# SM3320-BATT-EV.net
KiCad netlist of a schematic drawn in Altium Designer
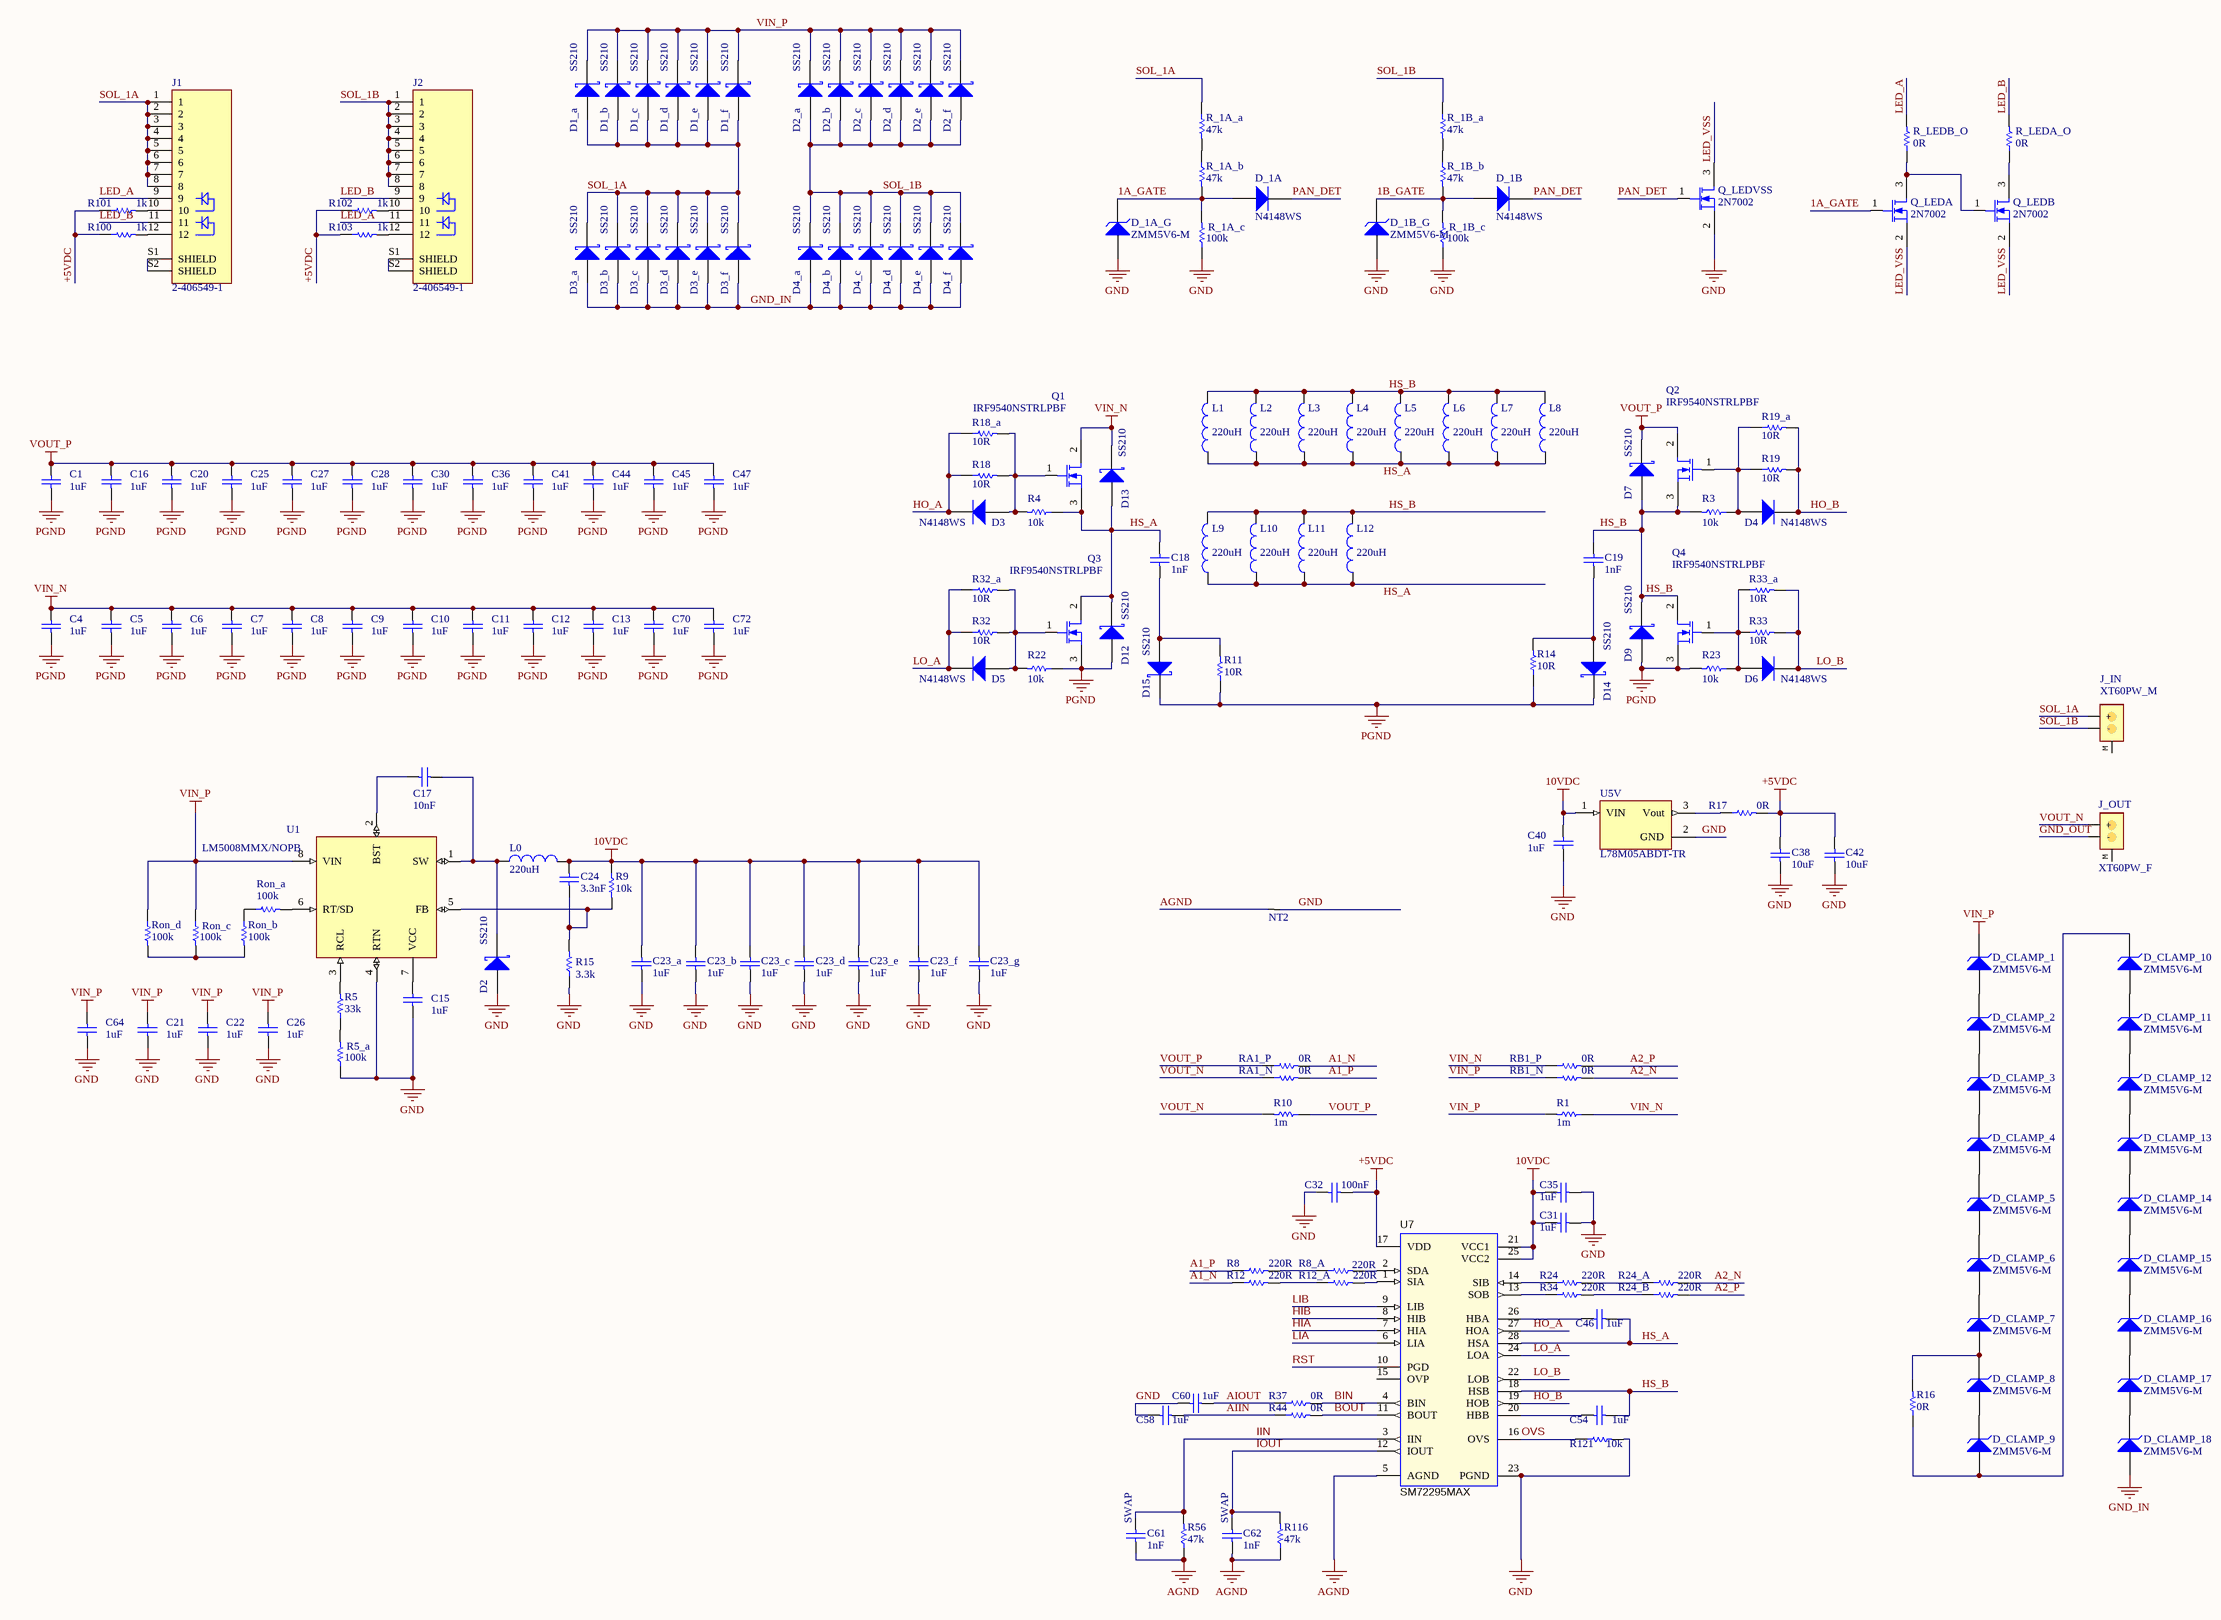
[diagram p0: SM3320-BATT-EV.SchDoc]

(export (version "E")
  (design (tool "Eeschema 10.0.6"))
  (components
    (comp (ref "C1")
      (value "1uF")
      (footprint "C_1206")
      (description "C - CAPACITOR - MLCC - 1uF - 100V - 1206 - X7R")
      (fields (field (name "LCSC PART #") "C91151") (field (name "Comment") "1206B105K101NT"))
      (libsource (lib "JLC_PCB") (part "1206B105K101NT"))
    )
    (comp (ref "C4")
      (value "1uF")
      (footprint "C_1206")
      (description "C - CAPACITOR - MLCC - 1uF - 100V - 1206 - X7R")
      (fields (field (name "LCSC PART #") "C91151") (field (name "Comment") "1206B105K101NT"))
      (libsource (lib "JLC_PCB") (part "1206B105K101NT"))
    )
    (comp (ref "C5")
      (value "1uF")
      (footprint "C_1206")
      (description "C - CAPACITOR - MLCC - 1uF - 100V - 1206 - X7R")
      (fields (field (name "LCSC PART #") "C91151") (field (name "Comment") "1206B105K101NT"))
      (libsource (lib "JLC_PCB") (part "1206B105K101NT"))
    )
    (comp (ref "C6")
      (value "1uF")
      (footprint "C_1206")
      (description "C - CAPACITOR - MLCC - 1uF - 100V - 1206 - X7R")
      (fields (field (name "LCSC PART #") "C91151") (field (name "Comment") "1206B105K101NT"))
      (libsource (lib "JLC_PCB") (part "1206B105K101NT"))
    )
    (comp (ref "C7")
      (value "1uF")
      (footprint "C_1206")
      (description "C - CAPACITOR - MLCC - 1uF - 100V - 1206 - X7R")
      (fields (field (name "LCSC PART #") "C91151") (field (name "Comment") "1206B105K101NT"))
      (libsource (lib "JLC_PCB") (part "1206B105K101NT"))
    )
    (comp (ref "C8")
      (value "1uF")
      (footprint "C_1206")
      (description "C - CAPACITOR - MLCC - 1uF - 100V - 1206 - X7R")
      (fields (field (name "LCSC PART #") "C91151") (field (name "Comment") "1206B105K101NT"))
      (libsource (lib "JLC_PCB") (part "1206B105K101NT"))
    )
    (comp (ref "C9")
      (value "1uF")
      (footprint "C_1206")
      (description "C - CAPACITOR - MLCC - 1uF - 100V - 1206 - X7R")
      (fields (field (name "LCSC PART #") "C91151") (field (name "Comment") "1206B105K101NT"))
      (libsource (lib "JLC_PCB") (part "1206B105K101NT"))
    )
    (comp (ref "C10")
      (value "1uF")
      (footprint "C_1206")
      (description "C - CAPACITOR - MLCC - 1uF - 100V - 1206 - X7R")
      (fields (field (name "LCSC PART #") "C91151") (field (name "Comment") "1206B105K101NT"))
      (libsource (lib "JLC_PCB") (part "1206B105K101NT"))
    )
    (comp (ref "C11")
      (value "1uF")
      (footprint "C_1206")
      (description "C - CAPACITOR - MLCC - 1uF - 100V - 1206 - X7R")
      (fields (field (name "LCSC PART #") "C91151") (field (name "Comment") "1206B105K101NT"))
      (libsource (lib "JLC_PCB") (part "1206B105K101NT"))
    )
    (comp (ref "C12")
      (value "1uF")
      (footprint "C_1206")
      (description "C - CAPACITOR - MLCC - 1uF - 100V - 1206 - X7R")
      (fields (field (name "LCSC PART #") "C91151") (field (name "Comment") "1206B105K101NT"))
      (libsource (lib "JLC_PCB") (part "1206B105K101NT"))
    )
    (comp (ref "C13")
      (value "1uF")
      (footprint "C_1206")
      (description "C - CAPACITOR - MLCC - 1uF - 100V - 1206 - X7R")
      (fields (field (name "LCSC PART #") "C91151") (field (name "Comment") "1206B105K101NT"))
      (libsource (lib "JLC_PCB") (part "1206B105K101NT"))
    )
    (comp (ref "C15")
      (value "1uF")
      (footprint "C_0402")
      (description "C - CAPACITOR - MLCC - 1uF - 25V - 0402")
      (fields (field (name "LCSC PART #") "C52923") (field (name "Comment") "CL05A105KA5NQNC"))
      (libsource (lib "JLC_PCB") (part "CL05A105KA5NQNC"))
    )
    (comp (ref "C16")
      (value "1uF")
      (footprint "C_1206")
      (description "C - CAPACITOR - MLCC - 1uF - 100V - 1206 - X7R")
      (fields (field (name "LCSC PART #") "C91151") (field (name "Comment") "1206B105K101NT"))
      (libsource (lib "JLC_PCB") (part "1206B105K101NT"))
    )
    (comp (ref "C17")
      (value "10nF")
      (footprint "C_0402")
      (description "C - CAPACITOR - MLCC - 10nF - 50V - 0402")
      (fields (field (name "LCSC PART #") "C15195") (field (name "Comment") "CL05B103KB5NNNC"))
      (libsource (lib "JLC_PCB") (part "CL05B103KB5NNNC"))
    )
    (comp (ref "C18")
      (value "1nF")
      (footprint "C_1206")
      (description "C - CAPACITOR - MLCC - 1nF - 2000V - 1206 - X7R")
      (fields (field (name "LCSC PART #") "C9196") (field (name "Comment") "1206B102K202NT"))
      (libsource (lib "JLC_PCB") (part "1206B102K202NT"))
    )
    (comp (ref "C19")
      (value "1nF")
      (footprint "C_1206")
      (description "C - CAPACITOR - MLCC - 1nF - 2000V - 1206 - X7R")
      (fields (field (name "LCSC PART #") "C9196") (field (name "Comment") "1206B102K202NT"))
      (libsource (lib "JLC_PCB") (part "1206B102K202NT"))
    )
    (comp (ref "C20")
      (value "1uF")
      (footprint "C_1206")
      (description "C - CAPACITOR - MLCC - 1uF - 100V - 1206 - X7R")
      (fields (field (name "LCSC PART #") "C91151") (field (name "Comment") "1206B105K101NT"))
      (libsource (lib "JLC_PCB") (part "1206B105K101NT"))
    )
    (comp (ref "C21")
      (value "1uF")
      (footprint "C_1206")
      (description "C - CAPACITOR - MLCC - 1uF - 100V - 1206 - X7R")
      (fields (field (name "LCSC PART #") "C91151") (field (name "Comment") "1206B105K101NT"))
      (libsource (lib "JLC_PCB") (part "1206B105K101NT"))
    )
    (comp (ref "C22")
      (value "1uF")
      (footprint "C_1206")
      (description "C - CAPACITOR - MLCC - 1uF - 100V - 1206 - X7R")
      (fields (field (name "LCSC PART #") "C91151") (field (name "Comment") "1206B105K101NT"))
      (libsource (lib "JLC_PCB") (part "1206B105K101NT"))
    )
    (comp (ref "C23_a")
      (value "1uF")
      (footprint "C_0402")
      (description "C - CAPACITOR - MLCC - 1uF - 25V - 0402")
      (fields (field (name "LCSC PART #") "C52923") (field (name "Comment") "CL05A105KA5NQNC"))
      (libsource (lib "JLC_PCB") (part "CL05A105KA5NQNC"))
    )
    (comp (ref "C23_b")
      (value "1uF")
      (footprint "C_0402")
      (description "C - CAPACITOR - MLCC - 1uF - 25V - 0402")
      (fields (field (name "LCSC PART #") "C52923") (field (name "Comment") "CL05A105KA5NQNC"))
      (libsource (lib "JLC_PCB") (part "CL05A105KA5NQNC"))
    )
    (comp (ref "C23_c")
      (value "1uF")
      (footprint "C_0402")
      (description "C - CAPACITOR - MLCC - 1uF - 25V - 0402")
      (fields (field (name "LCSC PART #") "C52923") (field (name "Comment") "CL05A105KA5NQNC"))
      (libsource (lib "JLC_PCB") (part "CL05A105KA5NQNC"))
    )
    (comp (ref "C23_d")
      (value "1uF")
      (footprint "C_0402")
      (description "C - CAPACITOR - MLCC - 1uF - 25V - 0402")
      (fields (field (name "LCSC PART #") "C52923") (field (name "Comment") "CL05A105KA5NQNC"))
      (libsource (lib "JLC_PCB") (part "CL05A105KA5NQNC"))
    )
    (comp (ref "C23_e")
      (value "1uF")
      (footprint "C_0402")
      (description "C - CAPACITOR - MLCC - 1uF - 25V - 0402")
      (fields (field (name "LCSC PART #") "C52923") (field (name "Comment") "CL05A105KA5NQNC"))
      (libsource (lib "JLC_PCB") (part "CL05A105KA5NQNC"))
    )
    (comp (ref "C23_f")
      (value "1uF")
      (footprint "C_0402")
      (description "C - CAPACITOR - MLCC - 1uF - 25V - 0402")
      (fields (field (name "LCSC PART #") "C52923") (field (name "Comment") "CL05A105KA5NQNC"))
      (libsource (lib "JLC_PCB") (part "CL05A105KA5NQNC"))
    )
    (comp (ref "C23_g")
      (value "1uF")
      (footprint "C_0402")
      (description "C - CAPACITOR - MLCC - 1uF - 25V - 0402")
      (fields (field (name "LCSC PART #") "C52923") (field (name "Comment") "CL05A105KA5NQNC"))
      (libsource (lib "JLC_PCB") (part "CL05A105KA5NQNC"))
    )
    (comp (ref "C24")
      (value "3.3nF")
      (footprint "C_0402")
      (description "C - CAPACITOR - MLCC - 3.3nF - 50V - 0402")
      (fields (field (name "LCSC PART #") "C26404") (field (name "Comment") "CL05B332KB5NNNC"))
      (libsource (lib "JLC_PCB") (part "CL05B332KB5NNNC"))
    )
    (comp (ref "C25")
      (value "1uF")
      (footprint "C_1206")
      (description "C - CAPACITOR - MLCC - 1uF - 100V - 1206 - X7R")
      (fields (field (name "LCSC PART #") "C91151") (field (name "Comment") "1206B105K101NT"))
      (libsource (lib "JLC_PCB") (part "1206B105K101NT"))
    )
    (comp (ref "C26")
      (value "1uF")
      (footprint "C_1206")
      (description "C - CAPACITOR - MLCC - 1uF - 100V - 1206 - X7R")
      (fields (field (name "LCSC PART #") "C91151") (field (name "Comment") "1206B105K101NT"))
      (libsource (lib "JLC_PCB") (part "1206B105K101NT"))
    )
    (comp (ref "C27")
      (value "1uF")
      (footprint "C_1206")
      (description "C - CAPACITOR - MLCC - 1uF - 100V - 1206 - X7R")
      (fields (field (name "LCSC PART #") "C91151") (field (name "Comment") "1206B105K101NT"))
      (libsource (lib "JLC_PCB") (part "1206B105K101NT"))
    )
    (comp (ref "C28")
      (value "1uF")
      (footprint "C_1206")
      (description "C - CAPACITOR - MLCC - 1uF - 100V - 1206 - X7R")
      (fields (field (name "LCSC PART #") "C91151") (field (name "Comment") "1206B105K101NT"))
      (libsource (lib "JLC_PCB") (part "1206B105K101NT"))
    )
    (comp (ref "C30")
      (value "1uF")
      (footprint "C_1206")
      (description "C - CAPACITOR - MLCC - 1uF - 100V - 1206 - X7R")
      (fields (field (name "LCSC PART #") "C91151") (field (name "Comment") "1206B105K101NT"))
      (libsource (lib "JLC_PCB") (part "1206B105K101NT"))
    )
    (comp (ref "C31")
      (value "1uF")
      (footprint "C_0402")
      (description "C - CAPACITOR - MLCC - 1uF - 25V - 0402")
      (fields (field (name "LCSC PART #") "C52923") (field (name "Comment") "CL05A105KA5NQNC"))
      (libsource (lib "JLC_PCB") (part "CL05A105KA5NQNC"))
    )
    (comp (ref "C32")
      (value "100nF")
      (footprint "C_0402")
      (description "C - CAPACITOR - MLCC - 100nF - 16V - 0402")
      (fields (field (name "LCSC PART #") "C1525") (field (name "Comment") "CL05B104KO5NNNC"))
      (libsource (lib "JLC_PCB") (part "CL05B104KO5NNNC"))
    )
    (comp (ref "C35")
      (value "1uF")
      (footprint "C_0402")
      (description "C - CAPACITOR - MLCC - 1uF - 25V - 0402")
      (fields (field (name "LCSC PART #") "C52923") (field (name "Comment") "CL05A105KA5NQNC"))
      (libsource (lib "JLC_PCB") (part "CL05A105KA5NQNC"))
    )
    (comp (ref "C36")
      (value "1uF")
      (footprint "C_1206")
      (description "C - CAPACITOR - MLCC - 1uF - 100V - 1206 - X7R")
      (fields (field (name "LCSC PART #") "C91151") (field (name "Comment") "1206B105K101NT"))
      (libsource (lib "JLC_PCB") (part "1206B105K101NT"))
    )
    (comp (ref "C38")
      (value "10uF")
      (footprint "C_0402")
      (description "C - CAPACITOR - MLCC - 10uF - 6.3V - 0402")
      (fields (field (name "LCSC PART #") "C15525") (field (name "Comment") "CL05A106MQ5NUNC"))
      (libsource (lib "JLC_PCB") (part "CL05A106MQ5NUNC"))
    )
    (comp (ref "C40")
      (value "1uF")
      (footprint "C_0402")
      (description "C - CAPACITOR - MLCC - 1uF - 25V - 0402")
      (fields (field (name "LCSC PART #") "C52923") (field (name "Comment") "CL05A105KA5NQNC"))
      (libsource (lib "JLC_PCB") (part "CL05A105KA5NQNC"))
    )
    (comp (ref "C41")
      (value "1uF")
      (footprint "C_1206")
      (description "C - CAPACITOR - MLCC - 1uF - 100V - 1206 - X7R")
      (fields (field (name "LCSC PART #") "C91151") (field (name "Comment") "1206B105K101NT"))
      (libsource (lib "JLC_PCB") (part "1206B105K101NT"))
    )
    (comp (ref "C42")
      (value "10uF")
      (footprint "C_0402")
      (description "C - CAPACITOR - MLCC - 10uF - 6.3V - 0402")
      (fields (field (name "LCSC PART #") "C15525") (field (name "Comment") "CL05A106MQ5NUNC"))
      (libsource (lib "JLC_PCB") (part "CL05A106MQ5NUNC"))
    )
    (comp (ref "C44")
      (value "1uF")
      (footprint "C_1206")
      (description "C - CAPACITOR - MLCC - 1uF - 100V - 1206 - X7R")
      (fields (field (name "LCSC PART #") "C91151") (field (name "Comment") "1206B105K101NT"))
      (libsource (lib "JLC_PCB") (part "1206B105K101NT"))
    )
    (comp (ref "C45")
      (value "1uF")
      (footprint "C_1206")
      (description "C - CAPACITOR - MLCC - 1uF - 100V - 1206 - X7R")
      (fields (field (name "LCSC PART #") "C91151") (field (name "Comment") "1206B105K101NT"))
      (libsource (lib "JLC_PCB") (part "1206B105K101NT"))
    )
    (comp (ref "C46")
      (value "1uF")
      (footprint "C_0402")
      (description "C - CAPACITOR - MLCC - 1uF - 25V - 0402")
      (fields (field (name "LCSC PART #") "C52923") (field (name "Comment") "CL05A105KA5NQNC"))
      (libsource (lib "JLC_PCB") (part "CL05A105KA5NQNC"))
    )
    (comp (ref "C47")
      (value "1uF")
      (footprint "C_1206")
      (description "C - CAPACITOR - MLCC - 1uF - 100V - 1206 - X7R")
      (fields (field (name "LCSC PART #") "C91151") (field (name "Comment") "1206B105K101NT"))
      (libsource (lib "JLC_PCB") (part "1206B105K101NT"))
    )
    (comp (ref "C54")
      (value "1uF")
      (footprint "C_0402")
      (description "C - CAPACITOR - MLCC - 1uF - 25V - 0402")
      (fields (field (name "LCSC PART #") "C52923") (field (name "Comment") "CL05A105KA5NQNC"))
      (libsource (lib "JLC_PCB") (part "CL05A105KA5NQNC"))
    )
    (comp (ref "C58")
      (value "1uF")
      (footprint "C_0402")
      (description "C - CAPACITOR - MLCC - 1uF - 25V - 0402")
      (fields (field (name "LCSC PART #") "C52923") (field (name "Comment") "CL05A105KA5NQNC"))
      (libsource (lib "JLC_PCB") (part "CL05A105KA5NQNC"))
    )
    (comp (ref "C60")
      (value "1uF")
      (footprint "C_0402")
      (description "C - CAPACITOR - MLCC - 1uF - 25V - 0402")
      (fields (field (name "LCSC PART #") "C52923") (field (name "Comment") "CL05A105KA5NQNC"))
      (libsource (lib "JLC_PCB") (part "CL05A105KA5NQNC"))
    )
    (comp (ref "C61")
      (value "1nF")
      (footprint "C_0402")
      (description "C - CAPACITOR - MLCC - 1nF - 50V - 0402")
      (fields (field (name "LCSC PART #") "C1523") (field (name "Comment") "0402B102K500NT"))
      (libsource (lib "JLC_PCB") (part "0402B102K500NT"))
    )
    (comp (ref "C62")
      (value "1nF")
      (footprint "C_0402")
      (description "C - CAPACITOR - MLCC - 1nF - 50V - 0402")
      (fields (field (name "LCSC PART #") "C1523") (field (name "Comment") "0402B102K500NT"))
      (libsource (lib "JLC_PCB") (part "0402B102K500NT"))
    )
    (comp (ref "C64")
      (value "1uF")
      (footprint "C_1206")
      (description "C - CAPACITOR - MLCC - 1uF - 100V - 1206 - X7R")
      (fields (field (name "LCSC PART #") "C91151") (field (name "Comment") "1206B105K101NT"))
      (libsource (lib "JLC_PCB") (part "1206B105K101NT"))
    )
    (comp (ref "C70")
      (value "1uF")
      (footprint "C_1206")
      (description "C - CAPACITOR - MLCC - 1uF - 100V - 1206 - X7R")
      (fields (field (name "LCSC PART #") "C91151") (field (name "Comment") "1206B105K101NT"))
      (libsource (lib "JLC_PCB") (part "1206B105K101NT"))
    )
    (comp (ref "C72")
      (value "1uF")
      (footprint "C_1206")
      (description "C - CAPACITOR - MLCC - 1uF - 100V - 1206 - X7R")
      (fields (field (name "LCSC PART #") "C91151") (field (name "Comment") "1206B105K101NT"))
      (libsource (lib "JLC_PCB") (part "1206B105K101NT"))
    )
    (comp (ref "D1_a")
      (value "SS210")
      (footprint "DO-214AC")
      (description "D - DIODE - SCHOTTKY - 100V - 2A")
      (fields (field (name "LCSC PART #") "C14996"))
      (libsource (lib "JLC_PCB") (part "SS210"))
    )
    (comp (ref "D1_b")
      (value "SS210")
      (footprint "DO-214AC")
      (description "D - DIODE - SCHOTTKY - 100V - 2A")
      (fields (field (name "LCSC PART #") "C14996"))
      (libsource (lib "JLC_PCB") (part "SS210"))
    )
    (comp (ref "D1_c")
      (value "SS210")
      (footprint "DO-214AC")
      (description "D - DIODE - SCHOTTKY - 100V - 2A")
      (fields (field (name "LCSC PART #") "C14996"))
      (libsource (lib "JLC_PCB") (part "SS210"))
    )
    (comp (ref "D1_d")
      (value "SS210")
      (footprint "DO-214AC")
      (description "D - DIODE - SCHOTTKY - 100V - 2A")
      (fields (field (name "LCSC PART #") "C14996"))
      (libsource (lib "JLC_PCB") (part "SS210"))
    )
    (comp (ref "D1_e")
      (value "SS210")
      (footprint "DO-214AC")
      (description "D - DIODE - SCHOTTKY - 100V - 2A")
      (fields (field (name "LCSC PART #") "C14996"))
      (libsource (lib "JLC_PCB") (part "SS210"))
    )
    (comp (ref "D1_f")
      (value "SS210")
      (footprint "DO-214AC")
      (description "D - DIODE - SCHOTTKY - 100V - 2A")
      (fields (field (name "LCSC PART #") "C14996"))
      (libsource (lib "JLC_PCB") (part "SS210"))
    )
    (comp (ref "D2")
      (value "SS210")
      (footprint "DO-214AC")
      (description "D - DIODE - SCHOTTKY - 100V - 2A")
      (fields (field (name "LCSC PART #") "C14996"))
      (libsource (lib "JLC_PCB") (part "SS210"))
    )
    (comp (ref "D2_a")
      (value "SS210")
      (footprint "DO-214AC")
      (description "D - DIODE - SCHOTTKY - 100V - 2A")
      (fields (field (name "LCSC PART #") "C14996"))
      (libsource (lib "JLC_PCB") (part "SS210"))
    )
    (comp (ref "D2_b")
      (value "SS210")
      (footprint "DO-214AC")
      (description "D - DIODE - SCHOTTKY - 100V - 2A")
      (fields (field (name "LCSC PART #") "C14996"))
      (libsource (lib "JLC_PCB") (part "SS210"))
    )
    (comp (ref "D2_c")
      (value "SS210")
      (footprint "DO-214AC")
      (description "D - DIODE - SCHOTTKY - 100V - 2A")
      (fields (field (name "LCSC PART #") "C14996"))
      (libsource (lib "JLC_PCB") (part "SS210"))
    )
    (comp (ref "D2_d")
      (value "SS210")
      (footprint "DO-214AC")
      (description "D - DIODE - SCHOTTKY - 100V - 2A")
      (fields (field (name "LCSC PART #") "C14996"))
      (libsource (lib "JLC_PCB") (part "SS210"))
    )
    (comp (ref "D2_e")
      (value "SS210")
      (footprint "DO-214AC")
      (description "D - DIODE - SCHOTTKY - 100V - 2A")
      (fields (field (name "LCSC PART #") "C14996"))
      (libsource (lib "JLC_PCB") (part "SS210"))
    )
    (comp (ref "D2_f")
      (value "SS210")
      (footprint "DO-214AC")
      (description "D - DIODE - SCHOTTKY - 100V - 2A")
      (fields (field (name "LCSC PART #") "C14996"))
      (libsource (lib "JLC_PCB") (part "SS210"))
    )
    (comp (ref "D3")
      (value "N4148WS")
      (footprint "SOD-323")
      (description "D - DIODE - FAST TRR - 100V - 150mA - 4ns")
      (fields (field (name "LCSC PART #") "C2128"))
      (libsource (lib "JLC_PCB") (part "N4148WS"))
    )
    (comp (ref "D3_a")
      (value "SS210")
      (footprint "DO-214AC")
      (description "D - DIODE - SCHOTTKY - 100V - 2A")
      (fields (field (name "LCSC PART #") "C14996"))
      (libsource (lib "JLC_PCB") (part "SS210"))
    )
    (comp (ref "D3_b")
      (value "SS210")
      (footprint "DO-214AC")
      (description "D - DIODE - SCHOTTKY - 100V - 2A")
      (fields (field (name "LCSC PART #") "C14996"))
      (libsource (lib "JLC_PCB") (part "SS210"))
    )
    (comp (ref "D3_c")
      (value "SS210")
      (footprint "DO-214AC")
      (description "D - DIODE - SCHOTTKY - 100V - 2A")
      (fields (field (name "LCSC PART #") "C14996"))
      (libsource (lib "JLC_PCB") (part "SS210"))
    )
    (comp (ref "D3_d")
      (value "SS210")
      (footprint "DO-214AC")
      (description "D - DIODE - SCHOTTKY - 100V - 2A")
      (fields (field (name "LCSC PART #") "C14996"))
      (libsource (lib "JLC_PCB") (part "SS210"))
    )
    (comp (ref "D3_e")
      (value "SS210")
      (footprint "DO-214AC")
      (description "D - DIODE - SCHOTTKY - 100V - 2A")
      (fields (field (name "LCSC PART #") "C14996"))
      (libsource (lib "JLC_PCB") (part "SS210"))
    )
    (comp (ref "D3_f")
      (value "SS210")
      (footprint "DO-214AC")
      (description "D - DIODE - SCHOTTKY - 100V - 2A")
      (fields (field (name "LCSC PART #") "C14996"))
      (libsource (lib "JLC_PCB") (part "SS210"))
    )
    (comp (ref "D4")
      (value "N4148WS")
      (footprint "SOD-323")
      (description "D - DIODE - FAST TRR - 100V - 150mA - 4ns")
      (fields (field (name "LCSC PART #") "C2128"))
      (libsource (lib "JLC_PCB") (part "N4148WS"))
    )
    (comp (ref "D4_a")
      (value "SS210")
      (footprint "DO-214AC")
      (description "D - DIODE - SCHOTTKY - 100V - 2A")
      (fields (field (name "LCSC PART #") "C14996"))
      (libsource (lib "JLC_PCB") (part "SS210"))
    )
    (comp (ref "D4_b")
      (value "SS210")
      (footprint "DO-214AC")
      (description "D - DIODE - SCHOTTKY - 100V - 2A")
      (fields (field (name "LCSC PART #") "C14996"))
      (libsource (lib "JLC_PCB") (part "SS210"))
    )
    (comp (ref "D4_c")
      (value "SS210")
      (footprint "DO-214AC")
      (description "D - DIODE - SCHOTTKY - 100V - 2A")
      (fields (field (name "LCSC PART #") "C14996"))
      (libsource (lib "JLC_PCB") (part "SS210"))
    )
    (comp (ref "D4_d")
      (value "SS210")
      (footprint "DO-214AC")
      (description "D - DIODE - SCHOTTKY - 100V - 2A")
      (fields (field (name "LCSC PART #") "C14996"))
      (libsource (lib "JLC_PCB") (part "SS210"))
    )
    (comp (ref "D4_e")
      (value "SS210")
      (footprint "DO-214AC")
      (description "D - DIODE - SCHOTTKY - 100V - 2A")
      (fields (field (name "LCSC PART #") "C14996"))
      (libsource (lib "JLC_PCB") (part "SS210"))
    )
    (comp (ref "D4_f")
      (value "SS210")
      (footprint "DO-214AC")
      (description "D - DIODE - SCHOTTKY - 100V - 2A")
      (fields (field (name "LCSC PART #") "C14996"))
      (libsource (lib "JLC_PCB") (part "SS210"))
    )
    (comp (ref "D5")
      (value "N4148WS")
      (footprint "SOD-323")
      (description "D - DIODE - FAST TRR - 100V - 150mA - 4ns")
      (fields (field (name "LCSC PART #") "C2128"))
      (libsource (lib "JLC_PCB") (part "N4148WS"))
    )
    (comp (ref "D6")
      (value "N4148WS")
      (footprint "SOD-323")
      (description "D - DIODE - FAST TRR - 100V - 150mA - 4ns")
      (fields (field (name "LCSC PART #") "C2128"))
      (libsource (lib "JLC_PCB") (part "N4148WS"))
    )
    (comp (ref "D7")
      (value "SS210")
      (footprint "DO-214AC")
      (description "D - DIODE - SCHOTTKY - 100V - 2A")
      (fields (field (name "LCSC PART #") "C14996"))
      (libsource (lib "JLC_PCB") (part "SS210"))
    )
    (comp (ref "D9")
      (value "SS210")
      (footprint "DO-214AC")
      (description "D - DIODE - SCHOTTKY - 100V - 2A")
      (fields (field (name "LCSC PART #") "C14996"))
      (libsource (lib "JLC_PCB") (part "SS210"))
    )
    (comp (ref "D12")
      (value "SS210")
      (footprint "DO-214AC")
      (description "D - DIODE - SCHOTTKY - 100V - 2A")
      (fields (field (name "LCSC PART #") "C14996"))
      (libsource (lib "JLC_PCB") (part "SS210"))
    )
    (comp (ref "D13")
      (value "SS210")
      (footprint "DO-214AC")
      (description "D - DIODE - SCHOTTKY - 100V - 2A")
      (fields (field (name "LCSC PART #") "C14996"))
      (libsource (lib "JLC_PCB") (part "SS210"))
    )
    (comp (ref "D14")
      (value "SS210")
      (footprint "DO-214AC")
      (description "D - DIODE - SCHOTTKY - 100V - 2A")
      (fields (field (name "LCSC PART #") "C14996"))
      (libsource (lib "JLC_PCB") (part "SS210"))
    )
    (comp (ref "D15")
      (value "SS210")
      (footprint "DO-214AC")
      (description "D - DIODE - SCHOTTKY - 100V - 2A")
      (fields (field (name "LCSC PART #") "C14996"))
      (libsource (lib "JLC_PCB") (part "SS210"))
    )
    (comp (ref "D_1A")
      (value "N4148WS")
      (footprint "SOD-323")
      (description "D - DIODE - FAST TRR - 100V - 150mA - 4ns")
      (fields (field (name "LCSC PART #") "C2128"))
      (libsource (lib "JLC_PCB") (part "N4148WS"))
    )
    (comp (ref "D_1A_G")
      (value "ZMM5V6-M")
      (footprint "DO-213AA")
      (description "D - DIODE - ZENER - 5.6V - 500mW")
      (fields (field (name "LCSC PART #") "C8062"))
      (libsource (lib "JLC_PCB") (part "ZMM5V6-M"))
    )
    (comp (ref "D_1B")
      (value "N4148WS")
      (footprint "SOD-323")
      (description "D - DIODE - FAST TRR - 100V - 150mA - 4ns")
      (fields (field (name "LCSC PART #") "C2128"))
      (libsource (lib "JLC_PCB") (part "N4148WS"))
    )
    (comp (ref "D_1B_G")
      (value "ZMM5V6-M")
      (footprint "DO-213AA")
      (description "D - DIODE - ZENER - 5.6V - 500mW")
      (fields (field (name "LCSC PART #") "C8062"))
      (libsource (lib "JLC_PCB") (part "ZMM5V6-M"))
    )
    (comp (ref "D_CLAMP_1")
      (value "ZMM5V6-M")
      (footprint "DO-213AA")
      (description "D - DIODE - ZENER - 5.6V - 500mW")
      (fields (field (name "LCSC PART #") "C8062"))
      (libsource (lib "JLC_PCB") (part "ZMM5V6-M"))
    )
    (comp (ref "D_CLAMP_2")
      (value "ZMM5V6-M")
      (footprint "DO-213AA")
      (description "D - DIODE - ZENER - 5.6V - 500mW")
      (fields (field (name "LCSC PART #") "C8062"))
      (libsource (lib "JLC_PCB") (part "ZMM5V6-M"))
    )
    (comp (ref "D_CLAMP_3")
      (value "ZMM5V6-M")
      (footprint "DO-213AA")
      (description "D - DIODE - ZENER - 5.6V - 500mW")
      (fields (field (name "LCSC PART #") "C8062"))
      (libsource (lib "JLC_PCB") (part "ZMM5V6-M"))
    )
    (comp (ref "D_CLAMP_4")
      (value "ZMM5V6-M")
      (footprint "DO-213AA")
      (description "D - DIODE - ZENER - 5.6V - 500mW")
      (fields (field (name "LCSC PART #") "C8062"))
      (libsource (lib "JLC_PCB") (part "ZMM5V6-M"))
    )
    (comp (ref "D_CLAMP_5")
      (value "ZMM5V6-M")
      (footprint "DO-213AA")
      (description "D - DIODE - ZENER - 5.6V - 500mW")
      (fields (field (name "LCSC PART #") "C8062"))
      (libsource (lib "JLC_PCB") (part "ZMM5V6-M"))
    )
    (comp (ref "D_CLAMP_6")
      (value "ZMM5V6-M")
      (footprint "DO-213AA")
      (description "D - DIODE - ZENER - 5.6V - 500mW")
      (fields (field (name "LCSC PART #") "C8062"))
      (libsource (lib "JLC_PCB") (part "ZMM5V6-M"))
    )
    (comp (ref "D_CLAMP_7")
      (value "ZMM5V6-M")
      (footprint "DO-213AA")
      (description "D - DIODE - ZENER - 5.6V - 500mW")
      (fields (field (name "LCSC PART #") "C8062"))
      (libsource (lib "JLC_PCB") (part "ZMM5V6-M"))
    )
    (comp (ref "D_CLAMP_8")
      (value "ZMM5V6-M")
      (footprint "DO-213AA")
      (description "D - DIODE - ZENER - 5.6V - 500mW")
      (fields (field (name "LCSC PART #") "C8062"))
      (libsource (lib "JLC_PCB") (part "ZMM5V6-M"))
    )
    (comp (ref "D_CLAMP_9")
      (value "ZMM5V6-M")
      (footprint "DO-213AA")
      (description "D - DIODE - ZENER - 5.6V - 500mW")
      (fields (field (name "LCSC PART #") "C8062"))
      (libsource (lib "JLC_PCB") (part "ZMM5V6-M"))
    )
    (comp (ref "D_CLAMP_10")
      (value "ZMM5V6-M")
      (footprint "DO-213AA")
      (description "D - DIODE - ZENER - 5.6V - 500mW")
      (fields (field (name "LCSC PART #") "C8062"))
      (libsource (lib "JLC_PCB") (part "ZMM5V6-M"))
    )
    (comp (ref "D_CLAMP_11")
      (value "ZMM5V6-M")
      (footprint "DO-213AA")
      (description "D - DIODE - ZENER - 5.6V - 500mW")
      (fields (field (name "LCSC PART #") "C8062"))
      (libsource (lib "JLC_PCB") (part "ZMM5V6-M"))
    )
    (comp (ref "D_CLAMP_12")
      (value "ZMM5V6-M")
      (footprint "DO-213AA")
      (description "D - DIODE - ZENER - 5.6V - 500mW")
      (fields (field (name "LCSC PART #") "C8062"))
      (libsource (lib "JLC_PCB") (part "ZMM5V6-M"))
    )
    (comp (ref "D_CLAMP_13")
      (value "ZMM5V6-M")
      (footprint "DO-213AA")
      (description "D - DIODE - ZENER - 5.6V - 500mW")
      (fields (field (name "LCSC PART #") "C8062"))
      (libsource (lib "JLC_PCB") (part "ZMM5V6-M"))
    )
    (comp (ref "D_CLAMP_14")
      (value "ZMM5V6-M")
      (footprint "DO-213AA")
      (description "D - DIODE - ZENER - 5.6V - 500mW")
      (fields (field (name "LCSC PART #") "C8062"))
      (libsource (lib "JLC_PCB") (part "ZMM5V6-M"))
    )
    (comp (ref "D_CLAMP_15")
      (value "ZMM5V6-M")
      (footprint "DO-213AA")
      (description "D - DIODE - ZENER - 5.6V - 500mW")
      (fields (field (name "LCSC PART #") "C8062"))
      (libsource (lib "JLC_PCB") (part "ZMM5V6-M"))
    )
    (comp (ref "D_CLAMP_16")
      (value "ZMM5V6-M")
      (footprint "DO-213AA")
      (description "D - DIODE - ZENER - 5.6V - 500mW")
      (fields (field (name "LCSC PART #") "C8062"))
      (libsource (lib "JLC_PCB") (part "ZMM5V6-M"))
    )
    (comp (ref "D_CLAMP_17")
      (value "ZMM5V6-M")
      (footprint "DO-213AA")
      (description "D - DIODE - ZENER - 5.6V - 500mW")
      (fields (field (name "LCSC PART #") "C8062"))
      (libsource (lib "JLC_PCB") (part "ZMM5V6-M"))
    )
    (comp (ref "D_CLAMP_18")
      (value "ZMM5V6-M")
      (footprint "DO-213AA")
      (description "D - DIODE - ZENER - 5.6V - 500mW")
      (fields (field (name "LCSC PART #") "C8062"))
      (libsource (lib "JLC_PCB") (part "ZMM5V6-M"))
    )
    (comp (ref "J1")
      (value "2-406549-1")
      (footprint "TE_2-406549-1")
      (description "J - JACK - ETHERNET - Right - THT")
      (fields (field (name "LCSC PART #") "C125068"))
      (libsource (lib "JLC_PCB") (part "2-406549-1"))
    )
    (comp (ref "J2")
      (value "2-406549-1")
      (footprint "TE_2-406549-1")
      (description "J - JACK - ETHERNET - Right - THT")
      (fields (field (name "LCSC PART #") "C125068"))
      (libsource (lib "JLC_PCB") (part "2-406549-1"))
    )
    (comp (ref "J_IN")
      (value "XT60PW_M")
      (footprint "XT60PW_M")
      (description "J - JACK - POWER - XT60 - RIGHT - MALE")
      (fields (field (name "LCSC PART #") "X"))
      (libsource (lib "JLC_PCB") (part "XT60PW_M"))
    )
    (comp (ref "J_OUT")
      (value "XT60PW_F")
      (footprint "XT60PW_F")
      (description "J - JACK - POWER - XT60 - RIGHT - FEMALE")
      (fields (field (name "LCSC PART #") "X"))
      (libsource (lib "JLC_PCB") (part "XT60PW_F"))
    )
    (comp (ref "L0")
      (value "220uH")
      (footprint "SRR1260")
      (description "L - INDUCTOR - 220uH - 1.6A - 12.5mm")
      (fields (field (name "LCSC PART #") "C169380") (field (name "Comment") "SWRB1207S-221MT"))
      (libsource (lib "JLC_PCB") (part "SWRB1207S-221MT"))
    )
    (comp (ref "L1")
      (value "220uH")
      (footprint "SRR1260")
      (description "L - INDUCTOR - 220uH - 1.6A - 12.5mm")
      (fields (field (name "LCSC PART #") "C169380") (field (name "Comment") "SWRB1207S-221MT"))
      (libsource (lib "JLC_PCB") (part "SWRB1207S-221MT"))
    )
    (comp (ref "L2")
      (value "220uH")
      (footprint "SRR1260")
      (description "L - INDUCTOR - 220uH - 1.6A - 12.5mm")
      (fields (field (name "LCSC PART #") "C169380") (field (name "Comment") "SWRB1207S-221MT"))
      (libsource (lib "JLC_PCB") (part "SWRB1207S-221MT"))
    )
    (comp (ref "L3")
      (value "220uH")
      (footprint "SRR1260")
      (description "L - INDUCTOR - 220uH - 1.6A - 12.5mm")
      (fields (field (name "LCSC PART #") "C169380") (field (name "Comment") "SWRB1207S-221MT"))
      (libsource (lib "JLC_PCB") (part "SWRB1207S-221MT"))
    )
    (comp (ref "L4")
      (value "220uH")
      (footprint "SRR1260")
      (description "L - INDUCTOR - 220uH - 1.6A - 12.5mm")
      (fields (field (name "LCSC PART #") "C169380") (field (name "Comment") "SWRB1207S-221MT"))
      (libsource (lib "JLC_PCB") (part "SWRB1207S-221MT"))
    )
    (comp (ref "L5")
      (value "220uH")
      (footprint "SRR1260")
      (description "L - INDUCTOR - 220uH - 1.6A - 12.5mm")
      (fields (field (name "LCSC PART #") "C169380") (field (name "Comment") "SWRB1207S-221MT"))
      (libsource (lib "JLC_PCB") (part "SWRB1207S-221MT"))
    )
    (comp (ref "L6")
      (value "220uH")
      (footprint "SRR1260")
      (description "L - INDUCTOR - 220uH - 1.6A - 12.5mm")
      (fields (field (name "LCSC PART #") "C169380") (field (name "Comment") "SWRB1207S-221MT"))
      (libsource (lib "JLC_PCB") (part "SWRB1207S-221MT"))
    )
    (comp (ref "L7")
      (value "220uH")
      (footprint "SRR1260")
      (description "L - INDUCTOR - 220uH - 1.6A - 12.5mm")
      (fields (field (name "LCSC PART #") "C169380") (field (name "Comment") "SWRB1207S-221MT"))
      (libsource (lib "JLC_PCB") (part "SWRB1207S-221MT"))
    )
    (comp (ref "L8")
      (value "220uH")
      (footprint "SRR1260")
      (description "L - INDUCTOR - 220uH - 1.6A - 12.5mm")
      (fields (field (name "LCSC PART #") "C169380") (field (name "Comment") "SWRB1207S-221MT"))
      (libsource (lib "JLC_PCB") (part "SWRB1207S-221MT"))
    )
    (comp (ref "L9")
      (value "220uH")
      (footprint "SRR1260")
      (description "L - INDUCTOR - 220uH - 1.6A - 12.5mm")
      (fields (field (name "LCSC PART #") "C169380") (field (name "Comment") "SWRB1207S-221MT"))
      (libsource (lib "JLC_PCB") (part "SWRB1207S-221MT"))
    )
    (comp (ref "L10")
      (value "220uH")
      (footprint "SRR1260")
      (description "L - INDUCTOR - 220uH - 1.6A - 12.5mm")
      (fields (field (name "LCSC PART #") "C169380") (field (name "Comment") "SWRB1207S-221MT"))
      (libsource (lib "JLC_PCB") (part "SWRB1207S-221MT"))
    )
    (comp (ref "L11")
      (value "220uH")
      (footprint "SRR1260")
      (description "L - INDUCTOR - 220uH - 1.6A - 12.5mm")
      (fields (field (name "LCSC PART #") "C169380") (field (name "Comment") "SWRB1207S-221MT"))
      (libsource (lib "JLC_PCB") (part "SWRB1207S-221MT"))
    )
    (comp (ref "L12")
      (value "220uH")
      (footprint "SRR1260")
      (description "L - INDUCTOR - 220uH - 1.6A - 12.5mm")
      (fields (field (name "LCSC PART #") "C169380") (field (name "Comment") "SWRB1207S-221MT"))
      (libsource (lib "JLC_PCB") (part "SWRB1207S-221MT"))
    )
    (comp (ref "NT2")
      (value "0")
      (footprint "NET_TIE")
      (description "R - Net Tie")
      (libsource (lib "JLC_PCB") (part "NET_TIE"))
    )
    (comp (ref "Q1")
      (value "IRF9540NSTRLPBF")
      (footprint "TO-263-3")
      (description "Q - TRANSISTOR - MOSFET (N) - 250V - 33A - 0.094R")
      (fields (field (name "LCSC PART #") "C33903"))
      (libsource (lib "JLC_PCB") (part "IRF9540NSTRLPBF"))
    )
    (comp (ref "Q2")
      (value "IRF9540NSTRLPBF")
      (footprint "TO-263-3")
      (description "Q - TRANSISTOR - MOSFET (N) - 250V - 33A - 0.094R")
      (fields (field (name "LCSC PART #") "C33903"))
      (libsource (lib "JLC_PCB") (part "IRF9540NSTRLPBF"))
    )
    (comp (ref "Q3")
      (value "IRF9540NSTRLPBF")
      (footprint "TO-263-3")
      (description "Q - TRANSISTOR - MOSFET (N) - 250V - 33A - 0.094R")
      (fields (field (name "LCSC PART #") "C33903"))
      (libsource (lib "JLC_PCB") (part "IRF9540NSTRLPBF"))
    )
    (comp (ref "Q4")
      (value "IRF9540NSTRLPBF")
      (footprint "TO-263-3")
      (description "Q - TRANSISTOR - MOSFET (N) - 250V - 33A - 0.094R")
      (fields (field (name "LCSC PART #") "C33903"))
      (libsource (lib "JLC_PCB") (part "IRF9540NSTRLPBF"))
    )
    (comp (ref "Q_LEDA")
      (value "2N7002")
      (footprint "TO-236AB")
      (description "Q - TRANSISTOR - MOSFET (N) - 60V - 200mW")
      (fields (field (name "LCSC PART #") "C8545"))
      (libsource (lib "JLC_PCB") (part "2N7002"))
    )
    (comp (ref "Q_LEDB")
      (value "2N7002")
      (footprint "TO-236AB")
      (description "Q - TRANSISTOR - MOSFET (N) - 60V - 200mW")
      (fields (field (name "LCSC PART #") "C8545"))
      (libsource (lib "JLC_PCB") (part "2N7002"))
    )
    (comp (ref "Q_LEDVSS")
      (value "2N7002")
      (footprint "TO-236AB")
      (description "Q - TRANSISTOR - MOSFET (N) - 60V - 200mW")
      (fields (field (name "LCSC PART #") "C8545"))
      (libsource (lib "JLC_PCB") (part "2N7002"))
    )
    (comp (ref "R1")
      (value "1m")
      (footprint "R_2512")
      (description "R - RESISTOR - SMD - 0.001R - 1% - 2512 - 2W - 50ppm/k")
      (fields (field (name "LCSC PART #") "C349153") (field (name "POWER") "2W"))
      (libsource (lib "JLC_PCB") (part "EWSL2512F1L00S9"))
    )
    (comp (ref "R3")
      (value "10k")
      (footprint "R_0402")
      (description "R - RESISTOR - SMD - 10k - 1% - 0402")
      (fields (field (name "LCSC PART #") "C25744") (field (name "Comment") "0402WGF1002TCE"))
      (libsource (lib "JLC_PCB") (part "0402WGF1002TCE"))
    )
    (comp (ref "R4")
      (value "10k")
      (footprint "R_0402")
      (description "R - RESISTOR - SMD - 10k - 1% - 0402")
      (fields (field (name "LCSC PART #") "C25744") (field (name "Comment") "0402WGF1002TCE"))
      (libsource (lib "JLC_PCB") (part "0402WGF1002TCE"))
    )
    (comp (ref "R5")
      (value "33k")
      (footprint "R_0402")
      (description "R - RESISTOR - SMD - 33k - 1% - 0402")
      (fields (field (name "LCSC PART #") "C25779") (field (name "Comment") "0402WGF3302TCE"))
      (libsource (lib "JLC_PCB") (part "0402WGF3302TCE"))
    )
    (comp (ref "R5_a")
      (value "100k")
      (footprint "R_0402")
      (description "R - RESISTOR - SMD - 100k - 1% -  0402")
      (fields (field (name "LCSC PART #") "C25741") (field (name "Comment") "0402WGF1003TCE"))
      (libsource (lib "JLC_PCB") (part "0402WGF1003TCE"))
    )
    (comp (ref "R8")
      (value "220R")
      (footprint "R_0402")
      (description "R - RESISTOR - SMD - 220R - 1% - 0402")
      (fields (field (name "LCSC PART #") "C25091") (field (name "Comment") "0402WGF2200TCE"))
      (libsource (lib "JLC_PCB") (part "0402WGF2200TCE"))
    )
    (comp (ref "R8_A")
      (value "220R")
      (footprint "R_0402")
      (description "R - RESISTOR - SMD - 220R - 1% - 0402")
      (fields (field (name "LCSC PART #") "C25091"))
      (libsource (lib "*") (part "0402WGF2200TCE"))
    )
    (comp (ref "R9")
      (value "10k")
      (footprint "R_0402")
      (description "R - RESISTOR - SMD - 10k - 1% - 0402")
      (fields (field (name "LCSC PART #") "C25744") (field (name "Comment") "0402WGF1002TCE"))
      (libsource (lib "JLC_PCB") (part "0402WGF1002TCE"))
    )
    (comp (ref "R10")
      (value "1m")
      (footprint "R_2512")
      (description "R - RESISTOR - SMD - 0.001R - 1% - 2512 - 2W - 50ppm/k")
      (fields (field (name "LCSC PART #") "C349153") (field (name "POWER") "2W"))
      (libsource (lib "JLC_PCB") (part "EWSL2512F1L00S9"))
    )
    (comp (ref "R11")
      (value "10R")
      (footprint "R_1206")
      (description "R - RESISTOR - SMD - 10R - 1% - 1206")
      (fields (field (name "LCSC PART #") "C17903") (field (name "Comment") "1206W4F100JT5E"))
      (libsource (lib "JLC_PCB") (part "1206W4F100JT5E"))
    )
    (comp (ref "R12")
      (value "220R")
      (footprint "R_0402")
      (description "R - RESISTOR - SMD - 220R - 1% - 0402")
      (fields (field (name "LCSC PART #") "C25091") (field (name "Comment") "0402WGF2200TCE"))
      (libsource (lib "JLC_PCB") (part "0402WGF2200TCE"))
    )
    (comp (ref "R12_A")
      (value "220R")
      (footprint "R_0402")
      (description "R - RESISTOR - SMD - 220R - 1% - 0402")
      (fields (field (name "LCSC PART #") "C25091") (field (name "Comment") "0402WGF2200TCE"))
      (libsource (lib "JLC_PCB") (part "0402WGF2200TCE"))
    )
    (comp (ref "R14")
      (value "10R")
      (footprint "R_1206")
      (description "R - RESISTOR - SMD - 10R - 1% - 1206")
      (fields (field (name "LCSC PART #") "C17903") (field (name "Comment") "1206W4F100JT5E"))
      (libsource (lib "JLC_PCB") (part "1206W4F100JT5E"))
    )
    (comp (ref "R15")
      (value "3.3k")
      (footprint "R_0402")
      (description "R - RESISTOR - SMD - 3.3k - 1% - 0402")
      (fields (field (name "LCSC PART #") "C25890") (field (name "Comment") "0402WGF3301TCE"))
      (libsource (lib "JLC_PCB") (part "0402WGF3301TCE"))
    )
    (comp (ref "R16")
      (value "0R")
      (footprint "R_0402")
      (description "R - RESISTOR - SMD - 0R - 1% - 0402")
      (fields (field (name "LCSC PART #") "C17168") (field (name "Comment") "0402WGF0000TCE"))
      (libsource (lib "JLC_PCB") (part "0402WGF0000TCE"))
    )
    (comp (ref "R17")
      (value "0R")
      (footprint "R_0402")
      (description "R - RESISTOR - SMD - 0R - 1% - 0402")
      (fields (field (name "LCSC PART #") "C17168") (field (name "Comment") "0402WGF0000TCE"))
      (libsource (lib "JLC_PCB") (part "0402WGF0000TCE"))
    )
    (comp (ref "R18")
      (value "10R")
      (footprint "R_0402")
      (description "R - RESISTOR - SMD - 10R - 1% - 0402")
      (fields (field (name "LCSC PART #") "C25077") (field (name "Comment") "0402WGF100JTCE"))
      (libsource (lib "JLC_PCB") (part "0402WGF100JTCE"))
    )
    (comp (ref "R18_a")
      (value "10R")
      (footprint "R_0402")
      (description "R - RESISTOR - SMD - 10R - 1% - 0402")
      (fields (field (name "LCSC PART #") "C25077") (field (name "Comment") "0402WGF100JTCE"))
      (libsource (lib "JLC_PCB") (part "0402WGF100JTCE"))
    )
    (comp (ref "R19")
      (value "10R")
      (footprint "R_0402")
      (description "R - RESISTOR - SMD - 10R - 1% - 0402")
      (fields (field (name "LCSC PART #") "C25077") (field (name "Comment") "0402WGF100JTCE"))
      (libsource (lib "JLC_PCB") (part "0402WGF100JTCE"))
    )
    (comp (ref "R19_a")
      (value "10R")
      (footprint "R_0402")
      (description "R - RESISTOR - SMD - 10R - 1% - 0402")
      (fields (field (name "LCSC PART #") "C25077") (field (name "Comment") "0402WGF100JTCE"))
      (libsource (lib "JLC_PCB") (part "0402WGF100JTCE"))
    )
    (comp (ref "R22")
      (value "10k")
      (footprint "R_0402")
      (description "R - RESISTOR - SMD - 10k - 1% - 0402")
      (fields (field (name "LCSC PART #") "C25744") (field (name "Comment") "0402WGF1002TCE"))
      (libsource (lib "JLC_PCB") (part "0402WGF1002TCE"))
    )
    (comp (ref "R23")
      (value "10k")
      (footprint "R_0402")
      (description "R - RESISTOR - SMD - 10k - 1% - 0402")
      (fields (field (name "LCSC PART #") "C25744") (field (name "Comment") "0402WGF1002TCE"))
      (libsource (lib "JLC_PCB") (part "0402WGF1002TCE"))
    )
    (comp (ref "R24")
      (value "220R")
      (footprint "R_0402")
      (description "R - RESISTOR - SMD - 220R - 1% - 0402")
      (fields (field (name "LCSC PART #") "C25091") (field (name "Comment") "0402WGF2200TCE"))
      (libsource (lib "JLC_PCB") (part "0402WGF2200TCE"))
    )
    (comp (ref "R24_A")
      (value "220R")
      (footprint "R_0402")
      (description "R - RESISTOR - SMD - 220R - 1% - 0402")
      (fields (field (name "LCSC PART #") "C25091") (field (name "Comment") "0402WGF2200TCE"))
      (libsource (lib "JLC_PCB") (part "0402WGF2200TCE"))
    )
    (comp (ref "R24_B")
      (value "220R")
      (footprint "R_0402")
      (description "R - RESISTOR - SMD - 220R - 1% - 0402")
      (fields (field (name "LCSC PART #") "C25091") (field (name "Comment") "0402WGF2200TCE"))
      (libsource (lib "JLC_PCB") (part "0402WGF2200TCE"))
    )
    (comp (ref "R32")
      (value "10R")
      (footprint "R_0402")
      (description "R - RESISTOR - SMD - 10R - 1% - 0402")
      (fields (field (name "LCSC PART #") "C25077") (field (name "Comment") "0402WGF100JTCE"))
      (libsource (lib "JLC_PCB") (part "0402WGF100JTCE"))
    )
    (comp (ref "R32_a")
      (value "10R")
      (footprint "R_0402")
      (description "R - RESISTOR - SMD - 10R - 1% - 0402")
      (fields (field (name "LCSC PART #") "C25077") (field (name "Comment") "0402WGF100JTCE"))
      (libsource (lib "JLC_PCB") (part "0402WGF100JTCE"))
    )
    (comp (ref "R33")
      (value "10R")
      (footprint "R_0402")
      (description "R - RESISTOR - SMD - 10R - 1% - 0402")
      (fields (field (name "LCSC PART #") "C25077") (field (name "Comment") "0402WGF100JTCE"))
      (libsource (lib "JLC_PCB") (part "0402WGF100JTCE"))
    )
    (comp (ref "R33_a")
      (value "10R")
      (footprint "R_0402")
      (description "R - RESISTOR - SMD - 10R - 1% - 0402")
      (fields (field (name "LCSC PART #") "C25077") (field (name "Comment") "0402WGF100JTCE"))
      (libsource (lib "JLC_PCB") (part "0402WGF100JTCE"))
    )
    (comp (ref "R34")
      (value "220R")
      (footprint "R_0402")
      (description "R - RESISTOR - SMD - 220R - 1% - 0402")
      (fields (field (name "LCSC PART #") "C25091") (field (name "Comment") "0402WGF2200TCE"))
      (libsource (lib "JLC_PCB") (part "0402WGF2200TCE"))
    )
    (comp (ref "R37")
      (value "0R")
      (footprint "R_0402")
      (description "R - RESISTOR - SMD - 0R - 1% - 0402")
      (fields (field (name "LCSC PART #") "C17168") (field (name "Comment") "0402WGF0000TCE"))
      (libsource (lib "JLC_PCB") (part "0402WGF0000TCE"))
    )
    (comp (ref "R44")
      (value "0R")
      (footprint "R_0402")
      (description "R - RESISTOR - SMD - 0R - 1% - 0402")
      (fields (field (name "LCSC PART #") "C17168") (field (name "Comment") "0402WGF0000TCE"))
      (libsource (lib "JLC_PCB") (part "0402WGF0000TCE"))
    )
    (comp (ref "R56")
      (value "47k")
      (footprint "R_0402")
      (description "R - RESISTOR - SMD - 47k - 1% - 0402")
      (fields (field (name "LCSC PART #") "C25792") (field (name "Comment") "0402WGF4702TCE"))
      (libsource (lib "JLC_PCB") (part "0402WGF4702TCE"))
    )
    (comp (ref "R100")
      (value "1k")
      (footprint "R_0402")
      (description "R - RESISTOR - SMD - 1k - 1% - 0402")
      (fields (field (name "LCSC PART #") "C11702") (field (name "Comment") "0402WGF1001TCE"))
      (libsource (lib "JLC_PCB") (part "0402WGF1001TCE"))
    )
    (comp (ref "R101")
      (value "1k")
      (footprint "R_0402")
      (description "R - RESISTOR - SMD - 1k - 1% - 0402")
      (fields (field (name "LCSC PART #") "C11702") (field (name "Comment") "0402WGF1001TCE"))
      (libsource (lib "JLC_PCB") (part "0402WGF1001TCE"))
    )
    (comp (ref "R102")
      (value "1k")
      (footprint "R_0402")
      (description "R - RESISTOR - SMD - 1k - 1% - 0402")
      (fields (field (name "LCSC PART #") "C11702") (field (name "Comment") "0402WGF1001TCE"))
      (libsource (lib "JLC_PCB") (part "0402WGF1001TCE"))
    )
    (comp (ref "R103")
      (value "1k")
      (footprint "R_0402")
      (description "R - RESISTOR - SMD - 1k - 1% - 0402")
      (fields (field (name "LCSC PART #") "C11702") (field (name "Comment") "0402WGF1001TCE"))
      (libsource (lib "JLC_PCB") (part "0402WGF1001TCE"))
    )
    (comp (ref "R116")
      (value "47k")
      (footprint "R_0402")
      (description "R - RESISTOR - SMD - 47k - 1% - 0402")
      (fields (field (name "LCSC PART #") "C25792") (field (name "Comment") "0402WGF4702TCE"))
      (libsource (lib "JLC_PCB") (part "0402WGF4702TCE"))
    )
    (comp (ref "R121")
      (value "10k")
      (footprint "R_0402")
      (description "R - RESISTOR - SMD - 10k - 1% - 0402")
      (fields (field (name "LCSC PART #") "C25744") (field (name "Comment") "0402WGF1002TCE"))
      (libsource (lib "JLC_PCB") (part "0402WGF1002TCE"))
    )
    (comp (ref "RA1_N")
      (value "0R")
      (footprint "R_0402")
      (description "R - RESISTOR - SMD - 0R - 1% - 0402")
      (fields (field (name "LCSC PART #") "C17168") (field (name "Comment") "0402WGF0000TCE"))
      (libsource (lib "JLC_PCB") (part "0402WGF0000TCE"))
    )
    (comp (ref "RA1_P")
      (value "0R")
      (footprint "R_0402")
      (description "R - RESISTOR - SMD - 0R - 1% - 0402")
      (fields (field (name "LCSC PART #") "C17168") (field (name "Comment") "0402WGF0000TCE"))
      (libsource (lib "JLC_PCB") (part "0402WGF0000TCE"))
    )
    (comp (ref "RB1_N")
      (value "0R")
      (footprint "R_0402")
      (description "R - RESISTOR - SMD - 0R - 1% - 0402")
      (fields (field (name "LCSC PART #") "C17168") (field (name "Comment") "0402WGF0000TCE"))
      (libsource (lib "JLC_PCB") (part "0402WGF0000TCE"))
    )
    (comp (ref "RB1_P")
      (value "0R")
      (footprint "R_0402")
      (description "R - RESISTOR - SMD - 0R - 1% - 0402")
      (fields (field (name "LCSC PART #") "C17168") (field (name "Comment") "0402WGF0000TCE"))
      (libsource (lib "JLC_PCB") (part "0402WGF0000TCE"))
    )
    (comp (ref "Ron_a")
      (value "100k")
      (footprint "R_0402")
      (description "R - RESISTOR - SMD - 100k - 1% -  0402")
      (fields (field (name "LCSC PART #") "C25741") (field (name "Comment") "0402WGF1003TCE"))
      (libsource (lib "JLC_PCB") (part "0402WGF1003TCE"))
    )
    (comp (ref "Ron_b")
      (value "100k")
      (footprint "R_0402")
      (description "R - RESISTOR - SMD - 100k - 1% -  0402")
      (fields (field (name "LCSC PART #") "C25741") (field (name "Comment") "0402WGF1003TCE"))
      (libsource (lib "JLC_PCB") (part "0402WGF1003TCE"))
    )
    (comp (ref "Ron_c")
      (value "100k")
      (footprint "R_0402")
      (description "R - RESISTOR - SMD - 100k - 1% -  0402")
      (fields (field (name "LCSC PART #") "C25741") (field (name "Comment") "0402WGF1003TCE"))
      (libsource (lib "JLC_PCB") (part "0402WGF1003TCE"))
    )
    (comp (ref "Ron_d")
      (value "100k")
      (footprint "R_0402")
      (description "R - RESISTOR - SMD - 100k - 1% -  0402")
      (fields (field (name "LCSC PART #") "C25741") (field (name "Comment") "0402WGF1003TCE"))
      (libsource (lib "JLC_PCB") (part "0402WGF1003TCE"))
    )
    (comp (ref "R_1A_a")
      (value "47k")
      (footprint "R_0402")
      (description "R - RESISTOR - SMD - 47k - 1% - 0402")
      (fields (field (name "LCSC PART #") "C25792") (field (name "Comment") "0402WGF4702TCE"))
      (libsource (lib "JLC_PCB") (part "0402WGF4702TCE"))
    )
    (comp (ref "R_1A_b")
      (value "47k")
      (footprint "R_0402")
      (description "R - RESISTOR - SMD - 47k - 1% - 0402")
      (fields (field (name "LCSC PART #") "C25792") (field (name "Comment") "0402WGF4702TCE"))
      (libsource (lib "JLC_PCB") (part "0402WGF4702TCE"))
    )
    (comp (ref "R_1A_c")
      (value "100k")
      (footprint "R_0402")
      (description "R - RESISTOR - SMD - 100k - 1% -  0402")
      (fields (field (name "LCSC PART #") "C25741") (field (name "Comment") "0402WGF1003TCE"))
      (libsource (lib "JLC_PCB") (part "0402WGF1003TCE"))
    )
    (comp (ref "R_1B_a")
      (value "47k")
      (footprint "R_0402")
      (description "R - RESISTOR - SMD - 47k - 1% - 0402")
      (fields (field (name "LCSC PART #") "C25792") (field (name "Comment") "0402WGF4702TCE"))
      (libsource (lib "JLC_PCB") (part "0402WGF4702TCE"))
    )
    (comp (ref "R_1B_b")
      (value "47k")
      (footprint "R_0402")
      (description "R - RESISTOR - SMD - 47k - 1% - 0402")
      (fields (field (name "LCSC PART #") "C25792") (field (name "Comment") "0402WGF4702TCE"))
      (libsource (lib "JLC_PCB") (part "0402WGF4702TCE"))
    )
    (comp (ref "R_1B_c")
      (value "100k")
      (footprint "R_0402")
      (description "R - RESISTOR - SMD - 100k - 1% -  0402")
      (fields (field (name "LCSC PART #") "C25741") (field (name "Comment") "0402WGF1003TCE"))
      (libsource (lib "JLC_PCB") (part "0402WGF1003TCE"))
    )
    (comp (ref "R_LEDA_O")
      (value "0R")
      (footprint "R_0402")
      (description "R - RESISTOR - SMD - 0R - 1% - 0402")
      (fields (field (name "LCSC PART #") "C17168") (field (name "Comment") "0402WGF0000TCE"))
      (libsource (lib "JLC_PCB") (part "0402WGF0000TCE"))
    )
    (comp (ref "R_LEDB_O")
      (value "0R")
      (footprint "R_0402")
      (description "R - RESISTOR - SMD - 0R - 1% - 0402")
      (fields (field (name "LCSC PART #") "C17168") (field (name "Comment") "0402WGF0000TCE"))
      (libsource (lib "JLC_PCB") (part "0402WGF0000TCE"))
    )
    (comp (ref "U1")
      (value "LM5008MMX/NOPB")
      (footprint "SOP65P490X110-8N")
      (description "U - IC - BUCK CONVERTER, ADJUSTABLE, 95V, 350mA")
      (libsource (lib "JLC_PCB") (part "LM5008MMX/NOPB"))
    )
    (comp (ref "U5V")
      (value "L78M05ABDT-TR")
      (footprint "TO-252AA")
      (description "U - IC - 5V Power Regulator")
      (fields (field (name "LCSC PART #") "C58069"))
      (libsource (lib "JLC_PCB") (part "L78M05ABDT-TR"))
    )
    (comp (ref "U7")
      (value "SM72295MAX")
      (footprint "M28B_M")
      (description "Photovoltaic Full Bridge Driver")
      (fields (field (name "MANUFACTURER") "National Semiconductor") (field (name "PARTNUMBER") "SM72295"))
      (libsource (lib "SM_ICs") (part "SM72295"))
    )
  )
  (nets
    (net (code "1") (name "+5VDC") (class "Default")
      (node (ref "C32") (pin "2") (pinfunction "2_2") (pintype "passive"))
      (node (ref "C38") (pin "2") (pinfunction "2_2") (pintype "passive"))
      (node (ref "C42") (pin "2") (pinfunction "2_2") (pintype "passive"))
      (node (ref "R100") (pin "1") (pinfunction "1_1") (pintype "passive"))
      (node (ref "R101") (pin "1") (pinfunction "1_1") (pintype "passive"))
      (node (ref "R102") (pin "1") (pinfunction "1_1") (pintype "passive"))
      (node (ref "R103") (pin "1") (pinfunction "1_1") (pintype "passive"))
      (node (ref "R17") (pin "2") (pinfunction "2_2") (pintype "passive"))
      (node (ref "U7") (pin "17") (pinfunction "VDD_17") (pintype "power_in"))
    )
    (net (code "2") (name "/1A_GATE") (class "Default")
      (node (ref "D_1A") (pin "2") (pinfunction "A_2") (pintype "passive"))
      (node (ref "D_1A_G") (pin "1") (pinfunction "K_1") (pintype "passive"))
      (node (ref "Q_LEDA") (pin "1") (pinfunction "G_1") (pintype "passive"))
      (node (ref "R_1A_b") (pin "2") (pinfunction "2_2") (pintype "passive"))
      (node (ref "R_1A_c") (pin "2") (pinfunction "2_2") (pintype "passive"))
    )
    (net (code "3") (name "/1B_GATE") (class "Default")
      (node (ref "D_1B") (pin "2") (pinfunction "A_2") (pintype "passive"))
      (node (ref "D_1B_G") (pin "1") (pinfunction "K_1") (pintype "passive"))
      (node (ref "R_1B_b") (pin "2") (pinfunction "2_2") (pintype "passive"))
      (node (ref "R_1B_c") (pin "2") (pinfunction "2_2") (pintype "passive"))
    )
    (net (code "4") (name "/A1_N") (class "Default")
      (node (ref "R12") (pin "1") (pinfunction "1_1") (pintype "passive"))
      (node (ref "RA1_P") (pin "2") (pinfunction "2_2") (pintype "passive"))
    )
    (net (code "5") (name "/A1_P") (class "Default")
      (node (ref "R8") (pin "1") (pinfunction "1_1") (pintype "passive"))
      (node (ref "RA1_N") (pin "2") (pinfunction "2_2") (pintype "passive"))
    )
    (net (code "6") (name "/A2_N") (class "Default")
      (node (ref "R24_A") (pin "2") (pinfunction "2_2") (pintype "passive"))
      (node (ref "RB1_N") (pin "2") (pinfunction "2_2") (pintype "passive"))
    )
    (net (code "7") (name "/A2_P") (class "Default")
      (node (ref "R24_B") (pin "2") (pinfunction "2_2") (pintype "passive"))
      (node (ref "RB1_P") (pin "2") (pinfunction "2_2") (pintype "passive"))
    )
    (net (code "8") (name "/AIIN") (class "Default")
      (node (ref "C58") (pin "2") (pinfunction "2_2") (pintype "passive"))
      (node (ref "R44") (pin "1") (pinfunction "1_1") (pintype "passive"))
    )
    (net (code "9") (name "/AIOUT") (class "Default")
      (node (ref "C60") (pin "2") (pinfunction "2_2") (pintype "passive"))
      (node (ref "R37") (pin "1") (pinfunction "1_1") (pintype "passive"))
    )
    (net (code "10") (name "/BIN") (class "Default")
      (node (ref "R37") (pin "2") (pinfunction "2_2") (pintype "passive"))
      (node (ref "U7") (pin "4") (pinfunction "BIN_4") (pintype "output"))
    )
    (net (code "11") (name "/BOUT") (class "Default")
      (node (ref "R44") (pin "2") (pinfunction "2_2") (pintype "passive"))
      (node (ref "U7") (pin "11") (pinfunction "BOUT_11") (pintype "output"))
    )
    (net (code "12") (name "/GND_OUT") (class "Default")
      (node (ref "J_OUT") (pin "MINUS") (pinfunction "-_MINUS") (pintype "passive"))
    )
    (net (code "13") (name "/HIA") (class "Default")
      (node (ref "U7") (pin "7") (pinfunction "HIA_7") (pintype "input"))
    )
    (net (code "14") (name "/HIB") (class "Default")
      (node (ref "U7") (pin "8") (pinfunction "HIB_8") (pintype "input"))
    )
    (net (code "15") (name "/HO_A") (class "Default")
      (node (ref "D3") (pin "1") (pinfunction "K_1") (pintype "passive"))
      (node (ref "R18") (pin "1") (pinfunction "1_1") (pintype "passive"))
      (node (ref "R18_a") (pin "1") (pinfunction "1_1") (pintype "passive"))
      (node (ref "U7") (pin "27") (pinfunction "HOA_27") (pintype "output"))
    )
    (net (code "16") (name "/HO_B") (class "Default")
      (node (ref "D4") (pin "1") (pinfunction "K_1") (pintype "passive"))
      (node (ref "R19") (pin "2") (pinfunction "2_2") (pintype "passive"))
      (node (ref "R19_a") (pin "2") (pinfunction "2_2") (pintype "passive"))
      (node (ref "U7") (pin "19") (pinfunction "HOB_19") (pintype "output"))
    )
    (net (code "17") (name "/HS_A") (class "Default")
      (node (ref "C18") (pin "2") (pinfunction "2_2") (pintype "passive"))
      (node (ref "C46") (pin "2") (pinfunction "2_2") (pintype "passive"))
      (node (ref "D12") (pin "1") (pinfunction "K_1") (pintype "passive"))
      (node (ref "D13") (pin "2") (pinfunction "A_2") (pintype "passive"))
      (node (ref "L1") (pin "1") (pinfunction "1_1") (pintype "passive"))
      (node (ref "L10") (pin "1") (pinfunction "1_1") (pintype "passive"))
      (node (ref "L11") (pin "1") (pinfunction "1_1") (pintype "passive"))
      (node (ref "L12") (pin "1") (pinfunction "1_1") (pintype "passive"))
      (node (ref "L2") (pin "1") (pinfunction "1_1") (pintype "passive"))
      (node (ref "L3") (pin "1") (pinfunction "1_1") (pintype "passive"))
      (node (ref "L4") (pin "1") (pinfunction "1_1") (pintype "passive"))
      (node (ref "L5") (pin "1") (pinfunction "1_1") (pintype "passive"))
      (node (ref "L6") (pin "1") (pinfunction "1_1") (pintype "passive"))
      (node (ref "L7") (pin "1") (pinfunction "1_1") (pintype "passive"))
      (node (ref "L8") (pin "1") (pinfunction "1_1") (pintype "passive"))
      (node (ref "L9") (pin "1") (pinfunction "1_1") (pintype "passive"))
      (node (ref "Q1") (pin "3") (pinfunction "S_3") (pintype "passive"))
      (node (ref "Q3") (pin "2") (pinfunction "D_2") (pintype "passive"))
      (node (ref "R4") (pin "1") (pinfunction "1_1") (pintype "passive"))
      (node (ref "U7") (pin "28") (pinfunction "HSA_28") (pintype "passive"))
    )
    (net (code "18") (name "/HS_B") (class "Default")
      (node (ref "C19") (pin "2") (pinfunction "2_2") (pintype "passive"))
      (node (ref "C54") (pin "2") (pinfunction "2_2") (pintype "passive"))
      (node (ref "D7") (pin "2") (pinfunction "A_2") (pintype "passive"))
      (node (ref "D9") (pin "1") (pinfunction "K_1") (pintype "passive"))
      (node (ref "L1") (pin "2") (pinfunction "2_2") (pintype "passive"))
      (node (ref "L10") (pin "2") (pinfunction "2_2") (pintype "passive"))
      (node (ref "L11") (pin "2") (pinfunction "2_2") (pintype "passive"))
      (node (ref "L12") (pin "2") (pinfunction "2_2") (pintype "passive"))
      (node (ref "L2") (pin "2") (pinfunction "2_2") (pintype "passive"))
      (node (ref "L3") (pin "2") (pinfunction "2_2") (pintype "passive"))
      (node (ref "L4") (pin "2") (pinfunction "2_2") (pintype "passive"))
      (node (ref "L5") (pin "2") (pinfunction "2_2") (pintype "passive"))
      (node (ref "L6") (pin "2") (pinfunction "2_2") (pintype "passive"))
      (node (ref "L7") (pin "2") (pinfunction "2_2") (pintype "passive"))
      (node (ref "L8") (pin "2") (pinfunction "2_2") (pintype "passive"))
      (node (ref "L9") (pin "2") (pinfunction "2_2") (pintype "passive"))
      (node (ref "Q2") (pin "3") (pinfunction "S_3") (pintype "passive"))
      (node (ref "Q4") (pin "2") (pinfunction "D_2") (pintype "passive"))
      (node (ref "R3") (pin "2") (pinfunction "2_2") (pintype "passive"))
      (node (ref "U7") (pin "18") (pinfunction "HSB_18") (pintype "passive"))
    )
    (net (code "19") (name "/IIN") (class "Default")
      (node (ref "C61") (pin "2") (pinfunction "2_2") (pintype "passive"))
      (node (ref "R56") (pin "2") (pinfunction "2_2") (pintype "passive"))
      (node (ref "U7") (pin "3") (pinfunction "IIN_3") (pintype "output"))
    )
    (net (code "20") (name "/IOUT") (class "Default")
      (node (ref "C62") (pin "2") (pinfunction "2_2") (pintype "passive"))
      (node (ref "R116") (pin "2") (pinfunction "2_2") (pintype "passive"))
      (node (ref "U7") (pin "12") (pinfunction "IOUT_12") (pintype "output"))
    )
    (net (code "21") (name "/LED_A") (class "Default")
      (node (ref "J1") (pin "9") (pinfunction "9_9") (pintype "passive"))
      (node (ref "J2") (pin "11") (pinfunction "11_11") (pintype "passive"))
      (node (ref "R_LEDB_O") (pin "2") (pinfunction "2_2") (pintype "passive"))
    )
    (net (code "22") (name "/LED_B") (class "Default")
      (node (ref "J1") (pin "11") (pinfunction "11_11") (pintype "passive"))
      (node (ref "J2") (pin "9") (pinfunction "9_9") (pintype "passive"))
      (node (ref "R_LEDA_O") (pin "2") (pinfunction "2_2") (pintype "passive"))
    )
    (net (code "23") (name "/LED_VSS") (class "Default")
      (node (ref "Q_LEDA") (pin "2") (pinfunction "S_2") (pintype "passive"))
      (node (ref "Q_LEDB") (pin "2") (pinfunction "S_2") (pintype "passive"))
      (node (ref "Q_LEDVSS") (pin "3") (pinfunction "D_3") (pintype "passive"))
    )
    (net (code "24") (name "/LIA") (class "Default")
      (node (ref "U7") (pin "6") (pinfunction "LIA_6") (pintype "input"))
    )
    (net (code "25") (name "/LIB") (class "Default")
      (node (ref "U7") (pin "9") (pinfunction "LIB_9") (pintype "input"))
    )
    (net (code "26") (name "/LO_A") (class "Default")
      (node (ref "D5") (pin "1") (pinfunction "K_1") (pintype "passive"))
      (node (ref "R32") (pin "1") (pinfunction "1_1") (pintype "passive"))
      (node (ref "R32_a") (pin "1") (pinfunction "1_1") (pintype "passive"))
      (node (ref "U7") (pin "24") (pinfunction "LOA_24") (pintype "output"))
    )
    (net (code "27") (name "/LO_B") (class "Default")
      (node (ref "D6") (pin "1") (pinfunction "K_1") (pintype "passive"))
      (node (ref "R33") (pin "2") (pinfunction "2_2") (pintype "passive"))
      (node (ref "R33_a") (pin "2") (pinfunction "2_2") (pintype "passive"))
      (node (ref "U7") (pin "22") (pinfunction "LOB_22") (pintype "output"))
    )
    (net (code "28") (name "/OVS") (class "Default")
      (node (ref "R121") (pin "1") (pinfunction "1_1") (pintype "passive"))
      (node (ref "U7") (pin "16") (pinfunction "OVS_16") (pintype "passive"))
    )
    (net (code "29") (name "/PAN_DET") (class "Default")
      (node (ref "D_1A") (pin "1") (pinfunction "K_1") (pintype "passive"))
      (node (ref "D_1B") (pin "1") (pinfunction "K_1") (pintype "passive"))
      (node (ref "Q_LEDVSS") (pin "1") (pinfunction "G_1") (pintype "passive"))
    )
    (net (code "30") (name "/RST") (class "Default")
      (node (ref "U7") (pin "10") (pinfunction "PGD_10") (pintype "open_collector"))
    )
    (net (code "31") (name "/SOL_1A") (class "Default")
      (node (ref "D1_a") (pin "2") (pinfunction "A_2") (pintype "passive"))
      (node (ref "D1_b") (pin "2") (pinfunction "A_2") (pintype "passive"))
      (node (ref "D1_c") (pin "2") (pinfunction "A_2") (pintype "passive"))
      (node (ref "D1_d") (pin "2") (pinfunction "A_2") (pintype "passive"))
      (node (ref "D1_e") (pin "2") (pinfunction "A_2") (pintype "passive"))
      (node (ref "D1_f") (pin "2") (pinfunction "A_2") (pintype "passive"))
      (node (ref "D3_a") (pin "1") (pinfunction "K_1") (pintype "passive"))
      (node (ref "D3_b") (pin "1") (pinfunction "K_1") (pintype "passive"))
      (node (ref "D3_c") (pin "1") (pinfunction "K_1") (pintype "passive"))
      (node (ref "D3_d") (pin "1") (pinfunction "K_1") (pintype "passive"))
      (node (ref "D3_e") (pin "1") (pinfunction "K_1") (pintype "passive"))
      (node (ref "D3_f") (pin "1") (pinfunction "K_1") (pintype "passive"))
      (node (ref "J1") (pin "1") (pinfunction "1_1") (pintype "passive"))
      (node (ref "J1") (pin "2") (pinfunction "2_2") (pintype "passive"))
      (node (ref "J1") (pin "3") (pinfunction "3_3") (pintype "passive"))
      (node (ref "J1") (pin "4") (pinfunction "4_4") (pintype "passive"))
      (node (ref "J1") (pin "5") (pinfunction "5_5") (pintype "passive"))
      (node (ref "J1") (pin "6") (pinfunction "6_6") (pintype "passive"))
      (node (ref "J1") (pin "7") (pinfunction "7_7") (pintype "passive"))
      (node (ref "J1") (pin "8") (pinfunction "8_8") (pintype "passive"))
      (node (ref "J_IN") (pin "PLUS") (pinfunction "+_PLUS") (pintype "passive"))
      (node (ref "R_1A_a") (pin "1") (pinfunction "1_1") (pintype "passive"))
    )
    (net (code "32") (name "/SOL_1B") (class "Default")
      (node (ref "D2_a") (pin "2") (pinfunction "A_2") (pintype "passive"))
      (node (ref "D2_b") (pin "2") (pinfunction "A_2") (pintype "passive"))
      (node (ref "D2_c") (pin "2") (pinfunction "A_2") (pintype "passive"))
      (node (ref "D2_d") (pin "2") (pinfunction "A_2") (pintype "passive"))
      (node (ref "D2_e") (pin "2") (pinfunction "A_2") (pintype "passive"))
      (node (ref "D2_f") (pin "2") (pinfunction "A_2") (pintype "passive"))
      (node (ref "D4_a") (pin "1") (pinfunction "K_1") (pintype "passive"))
      (node (ref "D4_b") (pin "1") (pinfunction "K_1") (pintype "passive"))
      (node (ref "D4_c") (pin "1") (pinfunction "K_1") (pintype "passive"))
      (node (ref "D4_d") (pin "1") (pinfunction "K_1") (pintype "passive"))
      (node (ref "D4_e") (pin "1") (pinfunction "K_1") (pintype "passive"))
      (node (ref "D4_f") (pin "1") (pinfunction "K_1") (pintype "passive"))
      (node (ref "J2") (pin "1") (pinfunction "1_1") (pintype "passive"))
      (node (ref "J2") (pin "2") (pinfunction "2_2") (pintype "passive"))
      (node (ref "J2") (pin "3") (pinfunction "3_3") (pintype "passive"))
      (node (ref "J2") (pin "4") (pinfunction "4_4") (pintype "passive"))
      (node (ref "J2") (pin "5") (pinfunction "5_5") (pintype "passive"))
      (node (ref "J2") (pin "6") (pinfunction "6_6") (pintype "passive"))
      (node (ref "J2") (pin "7") (pinfunction "7_7") (pintype "passive"))
      (node (ref "J2") (pin "8") (pinfunction "8_8") (pintype "passive"))
      (node (ref "J_IN") (pin "MINUS") (pinfunction "-_MINUS") (pintype "passive"))
      (node (ref "R_1B_a") (pin "1") (pinfunction "1_1") (pintype "passive"))
    )
    (net (code "33") (name "/VOUT_N") (class "Default")
      (node (ref "J_OUT") (pin "PLUS") (pinfunction "+_PLUS") (pintype "passive"))
      (node (ref "R10") (pin "2") (pinfunction "2_2") (pintype "passive"))
      (node (ref "RA1_N") (pin "1") (pinfunction "1_1") (pintype "passive"))
    )
    (net (code "34") (name "10VDC") (class "Default")
      (node (ref "C23_a") (pin "1") (pinfunction "1_1") (pintype "passive"))
      (node (ref "C23_b") (pin "1") (pinfunction "1_1") (pintype "passive"))
      (node (ref "C23_c") (pin "1") (pinfunction "1_1") (pintype "passive"))
      (node (ref "C23_d") (pin "1") (pinfunction "1_1") (pintype "passive"))
      (node (ref "C23_e") (pin "1") (pinfunction "1_1") (pintype "passive"))
      (node (ref "C23_f") (pin "1") (pinfunction "1_1") (pintype "passive"))
      (node (ref "C23_g") (pin "1") (pinfunction "1_1") (pintype "passive"))
      (node (ref "C24") (pin "2") (pinfunction "2_2") (pintype "passive"))
      (node (ref "C31") (pin "1") (pinfunction "1_1") (pintype "passive"))
      (node (ref "C35") (pin "1") (pinfunction "1_1") (pintype "passive"))
      (node (ref "C40") (pin "2") (pinfunction "2_2") (pintype "passive"))
      (node (ref "L0") (pin "2") (pinfunction "2_2") (pintype "passive"))
      (node (ref "R9") (pin "1") (pinfunction "1_1") (pintype "passive"))
      (node (ref "U5V") (pin "1") (pinfunction "VIN_1") (pintype "input"))
      (node (ref "U7") (pin "21") (pinfunction "VCC1_21") (pintype "power_in"))
      (node (ref "U7") (pin "25") (pinfunction "VCC2_25") (pintype "power_in"))
    )
    (net (code "35") (name "AGND") (class "Default")
      (node (ref "C61") (pin "1") (pinfunction "1_1") (pintype "passive"))
      (node (ref "C62") (pin "1") (pinfunction "1_1") (pintype "passive"))
      (node (ref "NT2") (pin "1") (pinfunction "1_1") (pintype "passive"))
      (node (ref "R116") (pin "1") (pinfunction "1_1") (pintype "passive"))
      (node (ref "R56") (pin "1") (pinfunction "1_1") (pintype "passive"))
      (node (ref "U7") (pin "5") (pinfunction "AGND_5") (pintype "power_in"))
    )
    (net (code "36") (name "GND") (class "Default")
      (node (ref "C15") (pin "2") (pinfunction "2_2") (pintype "passive"))
      (node (ref "C21") (pin "1") (pinfunction "1_1") (pintype "passive"))
      (node (ref "C22") (pin "1") (pinfunction "1_1") (pintype "passive"))
      (node (ref "C23_a") (pin "2") (pinfunction "2_2") (pintype "passive"))
      (node (ref "C23_b") (pin "2") (pinfunction "2_2") (pintype "passive"))
      (node (ref "C23_c") (pin "2") (pinfunction "2_2") (pintype "passive"))
      (node (ref "C23_d") (pin "2") (pinfunction "2_2") (pintype "passive"))
      (node (ref "C23_e") (pin "2") (pinfunction "2_2") (pintype "passive"))
      (node (ref "C23_f") (pin "2") (pinfunction "2_2") (pintype "passive"))
      (node (ref "C23_g") (pin "2") (pinfunction "2_2") (pintype "passive"))
      (node (ref "C26") (pin "1") (pinfunction "1_1") (pintype "passive"))
      (node (ref "C31") (pin "2") (pinfunction "2_2") (pintype "passive"))
      (node (ref "C32") (pin "1") (pinfunction "1_1") (pintype "passive"))
      (node (ref "C35") (pin "2") (pinfunction "2_2") (pintype "passive"))
      (node (ref "C38") (pin "1") (pinfunction "1_1") (pintype "passive"))
      (node (ref "C40") (pin "1") (pinfunction "1_1") (pintype "passive"))
      (node (ref "C42") (pin "1") (pinfunction "1_1") (pintype "passive"))
      (node (ref "C58") (pin "1") (pinfunction "1_1") (pintype "passive"))
      (node (ref "C60") (pin "1") (pinfunction "1_1") (pintype "passive"))
      (node (ref "C64") (pin "1") (pinfunction "1_1") (pintype "passive"))
      (node (ref "D2") (pin "2") (pinfunction "A_2") (pintype "passive"))
      (node (ref "D_1A_G") (pin "2") (pinfunction "A_2") (pintype "passive"))
      (node (ref "D_1B_G") (pin "2") (pinfunction "A_2") (pintype "passive"))
      (node (ref "NT2") (pin "2") (pinfunction "2_2") (pintype "passive"))
      (node (ref "Q_LEDVSS") (pin "2") (pinfunction "S_2") (pintype "passive"))
      (node (ref "R121") (pin "2") (pinfunction "2_2") (pintype "passive"))
      (node (ref "R15") (pin "1") (pinfunction "1_1") (pintype "passive"))
      (node (ref "R5_a") (pin "1") (pinfunction "1_1") (pintype "passive"))
      (node (ref "R_1A_c") (pin "1") (pinfunction "1_1") (pintype "passive"))
      (node (ref "R_1B_c") (pin "1") (pinfunction "1_1") (pintype "passive"))
      (node (ref "U1") (pin "4") (pinfunction "RTN_4") (pintype "bidirectional"))
      (node (ref "U5V") (pin "2") (pinfunction "GND_2") (pintype "power_in"))
      (node (ref "U7") (pin "23") (pinfunction "PGND_23") (pintype "power_in"))
    )
    (net (code "37") (name "GND_IN") (class "Default")
      (node (ref "D3_a") (pin "2") (pinfunction "A_2") (pintype "passive"))
      (node (ref "D3_b") (pin "2") (pinfunction "A_2") (pintype "passive"))
      (node (ref "D3_c") (pin "2") (pinfunction "A_2") (pintype "passive"))
      (node (ref "D3_d") (pin "2") (pinfunction "A_2") (pintype "passive"))
      (node (ref "D3_e") (pin "2") (pinfunction "A_2") (pintype "passive"))
      (node (ref "D3_f") (pin "2") (pinfunction "A_2") (pintype "passive"))
      (node (ref "D4_a") (pin "2") (pinfunction "A_2") (pintype "passive"))
      (node (ref "D4_b") (pin "2") (pinfunction "A_2") (pintype "passive"))
      (node (ref "D4_c") (pin "2") (pinfunction "A_2") (pintype "passive"))
      (node (ref "D4_d") (pin "2") (pinfunction "A_2") (pintype "passive"))
      (node (ref "D4_e") (pin "2") (pinfunction "A_2") (pintype "passive"))
      (node (ref "D4_f") (pin "2") (pinfunction "A_2") (pintype "passive"))
      (node (ref "D_CLAMP_18") (pin "2") (pinfunction "A_2") (pintype "passive"))
    )
    (net (code "38") (name "Net-(D2-K)") (class "Default")
      (node (ref "C17") (pin "2") (pinfunction "2_2") (pintype "passive"))
      (node (ref "D2") (pin "1") (pinfunction "K_1") (pintype "passive"))
      (node (ref "L0") (pin "1") (pinfunction "1_1") (pintype "passive"))
      (node (ref "U1") (pin "1") (pinfunction "SW_1") (pintype "bidirectional"))
    )
    (net (code "39") (name "Net-(D3-A)") (class "Default")
      (node (ref "D3") (pin "2") (pinfunction "A_2") (pintype "passive"))
      (node (ref "Q1") (pin "1") (pinfunction "G_1") (pintype "passive"))
      (node (ref "R18") (pin "2") (pinfunction "2_2") (pintype "passive"))
      (node (ref "R18_a") (pin "2") (pinfunction "2_2") (pintype "passive"))
      (node (ref "R4") (pin "2") (pinfunction "2_2") (pintype "passive"))
    )
    (net (code "40") (name "Net-(D4-A)") (class "Default")
      (node (ref "D4") (pin "2") (pinfunction "A_2") (pintype "passive"))
      (node (ref "Q2") (pin "1") (pinfunction "G_1") (pintype "passive"))
      (node (ref "R19") (pin "1") (pinfunction "1_1") (pintype "passive"))
      (node (ref "R19_a") (pin "1") (pinfunction "1_1") (pintype "passive"))
      (node (ref "R3") (pin "1") (pinfunction "1_1") (pintype "passive"))
    )
    (net (code "41") (name "Net-(D5-A)") (class "Default")
      (node (ref "D5") (pin "2") (pinfunction "A_2") (pintype "passive"))
      (node (ref "Q3") (pin "1") (pinfunction "G_1") (pintype "passive"))
      (node (ref "R22") (pin "2") (pinfunction "2_2") (pintype "passive"))
      (node (ref "R32") (pin "2") (pinfunction "2_2") (pintype "passive"))
      (node (ref "R32_a") (pin "2") (pinfunction "2_2") (pintype "passive"))
    )
    (net (code "42") (name "Net-(D6-A)") (class "Default")
      (node (ref "D6") (pin "2") (pinfunction "A_2") (pintype "passive"))
      (node (ref "Q4") (pin "1") (pinfunction "G_1") (pintype "passive"))
      (node (ref "R23") (pin "1") (pinfunction "1_1") (pintype "passive"))
      (node (ref "R33") (pin "1") (pinfunction "1_1") (pintype "passive"))
      (node (ref "R33_a") (pin "1") (pinfunction "1_1") (pintype "passive"))
    )
    (net (code "43") (name "Net-(D14-A)") (class "Default")
      (node (ref "C19") (pin "1") (pinfunction "1_1") (pintype "passive"))
      (node (ref "D14") (pin "2") (pinfunction "A_2") (pintype "passive"))
      (node (ref "R14") (pin "2") (pinfunction "2_2") (pintype "passive"))
    )
    (net (code "44") (name "Net-(D15-A)") (class "Default")
      (node (ref "C18") (pin "1") (pinfunction "1_1") (pintype "passive"))
      (node (ref "D15") (pin "2") (pinfunction "A_2") (pintype "passive"))
      (node (ref "R11") (pin "2") (pinfunction "2_2") (pintype "passive"))
    )
    (net (code "45") (name "Net-(D_CLAMP_1-A)") (class "Default")
      (node (ref "D_CLAMP_1") (pin "2") (pinfunction "A_2") (pintype "passive"))
      (node (ref "D_CLAMP_2") (pin "1") (pinfunction "K_1") (pintype "passive"))
    )
    (net (code "46") (name "Net-(D_CLAMP_2-A)") (class "Default")
      (node (ref "D_CLAMP_2") (pin "2") (pinfunction "A_2") (pintype "passive"))
      (node (ref "D_CLAMP_3") (pin "1") (pinfunction "K_1") (pintype "passive"))
    )
    (net (code "47") (name "Net-(D_CLAMP_3-A)") (class "Default")
      (node (ref "D_CLAMP_3") (pin "2") (pinfunction "A_2") (pintype "passive"))
      (node (ref "D_CLAMP_4") (pin "1") (pinfunction "K_1") (pintype "passive"))
    )
    (net (code "48") (name "Net-(D_CLAMP_4-A)") (class "Default")
      (node (ref "D_CLAMP_4") (pin "2") (pinfunction "A_2") (pintype "passive"))
      (node (ref "D_CLAMP_5") (pin "1") (pinfunction "K_1") (pintype "passive"))
    )
    (net (code "49") (name "Net-(D_CLAMP_5-A)") (class "Default")
      (node (ref "D_CLAMP_5") (pin "2") (pinfunction "A_2") (pintype "passive"))
      (node (ref "D_CLAMP_6") (pin "1") (pinfunction "K_1") (pintype "passive"))
    )
    (net (code "50") (name "Net-(D_CLAMP_6-A)") (class "Default")
      (node (ref "D_CLAMP_6") (pin "2") (pinfunction "A_2") (pintype "passive"))
      (node (ref "D_CLAMP_7") (pin "1") (pinfunction "K_1") (pintype "passive"))
    )
    (net (code "51") (name "Net-(D_CLAMP_7-A)") (class "Default")
      (node (ref "D_CLAMP_7") (pin "2") (pinfunction "A_2") (pintype "passive"))
      (node (ref "D_CLAMP_8") (pin "1") (pinfunction "K_1") (pintype "passive"))
      (node (ref "R16") (pin "2") (pinfunction "2_2") (pintype "passive"))
    )
    (net (code "52") (name "Net-(D_CLAMP_8-A)") (class "Default")
      (node (ref "D_CLAMP_8") (pin "2") (pinfunction "A_2") (pintype "passive"))
      (node (ref "D_CLAMP_9") (pin "1") (pinfunction "K_1") (pintype "passive"))
    )
    (net (code "53") (name "Net-(D_CLAMP_10-A)") (class "Default")
      (node (ref "D_CLAMP_10") (pin "2") (pinfunction "A_2") (pintype "passive"))
      (node (ref "D_CLAMP_11") (pin "1") (pinfunction "K_1") (pintype "passive"))
    )
    (net (code "54") (name "Net-(D_CLAMP_10-K)") (class "Default")
      (node (ref "D_CLAMP_10") (pin "1") (pinfunction "K_1") (pintype "passive"))
      (node (ref "D_CLAMP_9") (pin "2") (pinfunction "A_2") (pintype "passive"))
      (node (ref "R16") (pin "1") (pinfunction "1_1") (pintype "passive"))
    )
    (net (code "55") (name "Net-(D_CLAMP_11-A)") (class "Default")
      (node (ref "D_CLAMP_11") (pin "2") (pinfunction "A_2") (pintype "passive"))
      (node (ref "D_CLAMP_12") (pin "1") (pinfunction "K_1") (pintype "passive"))
    )
    (net (code "56") (name "Net-(D_CLAMP_12-A)") (class "Default")
      (node (ref "D_CLAMP_12") (pin "2") (pinfunction "A_2") (pintype "passive"))
      (node (ref "D_CLAMP_13") (pin "1") (pinfunction "K_1") (pintype "passive"))
    )
    (net (code "57") (name "Net-(D_CLAMP_13-A)") (class "Default")
      (node (ref "D_CLAMP_13") (pin "2") (pinfunction "A_2") (pintype "passive"))
      (node (ref "D_CLAMP_14") (pin "1") (pinfunction "K_1") (pintype "passive"))
    )
    (net (code "58") (name "Net-(D_CLAMP_14-A)") (class "Default")
      (node (ref "D_CLAMP_14") (pin "2") (pinfunction "A_2") (pintype "passive"))
      (node (ref "D_CLAMP_15") (pin "1") (pinfunction "K_1") (pintype "passive"))
    )
    (net (code "59") (name "Net-(D_CLAMP_15-A)") (class "Default")
      (node (ref "D_CLAMP_15") (pin "2") (pinfunction "A_2") (pintype "passive"))
      (node (ref "D_CLAMP_16") (pin "1") (pinfunction "K_1") (pintype "passive"))
    )
    (net (code "60") (name "Net-(D_CLAMP_16-A)") (class "Default")
      (node (ref "D_CLAMP_16") (pin "2") (pinfunction "A_2") (pintype "passive"))
      (node (ref "D_CLAMP_17") (pin "1") (pinfunction "K_1") (pintype "passive"))
    )
    (net (code "61") (name "Net-(D_CLAMP_17-A)") (class "Default")
      (node (ref "D_CLAMP_17") (pin "2") (pinfunction "A_2") (pintype "passive"))
      (node (ref "D_CLAMP_18") (pin "1") (pinfunction "K_1") (pintype "passive"))
    )
    (net (code "62") (name "Net-(J1-Pad10)") (class "Default")
      (node (ref "J1") (pin "10") (pinfunction "10_10") (pintype "passive"))
      (node (ref "R101") (pin "2") (pinfunction "2_2") (pintype "passive"))
    )
    (net (code "63") (name "Net-(J1-Pad12)") (class "Default")
      (node (ref "J1") (pin "12") (pinfunction "12_12") (pintype "passive"))
      (node (ref "R100") (pin "2") (pinfunction "2_2") (pintype "passive"))
    )
    (net (code "64") (name "Net-(J1-SHIELD-PadS1)") (class "Default")
      (node (ref "J1") (pin "S1") (pinfunction "SHIELD_S1") (pintype "passive"))
      (node (ref "J1") (pin "S2") (pinfunction "SHIELD_S2") (pintype "passive"))
    )
    (net (code "65") (name "Net-(J2-Pad10)") (class "Default")
      (node (ref "J2") (pin "10") (pinfunction "10_10") (pintype "passive"))
      (node (ref "R102") (pin "2") (pinfunction "2_2") (pintype "passive"))
    )
    (net (code "66") (name "Net-(J2-Pad12)") (class "Default")
      (node (ref "J2") (pin "12") (pinfunction "12_12") (pintype "passive"))
      (node (ref "R103") (pin "2") (pinfunction "2_2") (pintype "passive"))
    )
    (net (code "67") (name "Net-(J2-SHIELD-PadS1)") (class "Default")
      (node (ref "J2") (pin "S1") (pinfunction "SHIELD_S1") (pintype "passive"))
      (node (ref "J2") (pin "S2") (pinfunction "SHIELD_S2") (pintype "passive"))
    )
    (net (code "68") (name "Net-(Q_LEDA-D)") (class "Default")
      (node (ref "Q_LEDA") (pin "3") (pinfunction "D_3") (pintype "passive"))
      (node (ref "Q_LEDB") (pin "1") (pinfunction "G_1") (pintype "passive"))
      (node (ref "R_LEDB_O") (pin "1") (pinfunction "1_1") (pintype "passive"))
    )
    (net (code "69") (name "Net-(Q_LEDB-D)") (class "Default")
      (node (ref "Q_LEDB") (pin "3") (pinfunction "D_3") (pintype "passive"))
      (node (ref "R_LEDA_O") (pin "1") (pinfunction "1_1") (pintype "passive"))
    )
    (net (code "70") (name "Net-(R5-Pad1)") (class "Default")
      (node (ref "R5") (pin "1") (pinfunction "1_1") (pintype "passive"))
      (node (ref "R5_a") (pin "2") (pinfunction "2_2") (pintype "passive"))
    )
    (net (code "71") (name "Net-(R8-Pad2)") (class "Default")
      (node (ref "R8") (pin "2") (pinfunction "2_2") (pintype "passive"))
      (node (ref "R8_A") (pin "1") (pinfunction "1_1") (pintype "passive"))
    )
    (net (code "72") (name "Net-(R12-Pad2)") (class "Default")
      (node (ref "R12") (pin "2") (pinfunction "2_2") (pintype "passive"))
      (node (ref "R12_A") (pin "1") (pinfunction "1_1") (pintype "passive"))
    )
    (net (code "73") (name "Net-(R24-Pad2)") (class "Default")
      (node (ref "R24") (pin "2") (pinfunction "2_2") (pintype "passive"))
      (node (ref "R24_A") (pin "1") (pinfunction "1_1") (pintype "passive"))
    )
    (net (code "74") (name "Net-(R24_B-Pad1)") (class "Default")
      (node (ref "R24_B") (pin "1") (pinfunction "1_1") (pintype "passive"))
      (node (ref "R34") (pin "2") (pinfunction "2_2") (pintype "passive"))
    )
    (net (code "75") (name "Net-(R_1A_a-Pad2)") (class "Default")
      (node (ref "R_1A_a") (pin "2") (pinfunction "2_2") (pintype "passive"))
      (node (ref "R_1A_b") (pin "1") (pinfunction "1_1") (pintype "passive"))
    )
    (net (code "76") (name "Net-(R_1B_a-Pad2)") (class "Default")
      (node (ref "R_1B_a") (pin "2") (pinfunction "2_2") (pintype "passive"))
      (node (ref "R_1B_b") (pin "1") (pinfunction "1_1") (pintype "passive"))
    )
    (net (code "77") (name "Net-(Ron_a-Pad1)") (class "Default")
      (node (ref "Ron_a") (pin "1") (pinfunction "1_1") (pintype "passive"))
      (node (ref "Ron_b") (pin "1") (pinfunction "1_1") (pintype "passive"))
    )
    (net (code "78") (name "Net-(Ron_b-Pad2)") (class "Default")
      (node (ref "Ron_b") (pin "2") (pinfunction "2_2") (pintype "passive"))
      (node (ref "Ron_c") (pin "2") (pinfunction "2_2") (pintype "passive"))
      (node (ref "Ron_d") (pin "2") (pinfunction "2_2") (pintype "passive"))
    )
    (net (code "79") (name "Net-(U1-BST)") (class "Default")
      (node (ref "C17") (pin "1") (pinfunction "1_1") (pintype "passive"))
      (node (ref "U1") (pin "2") (pinfunction "BST_2") (pintype "bidirectional"))
    )
    (net (code "80") (name "Net-(U1-FB)") (class "Default")
      (node (ref "C24") (pin "1") (pinfunction "1_1") (pintype "passive"))
      (node (ref "R15") (pin "2") (pinfunction "2_2") (pintype "passive"))
      (node (ref "R9") (pin "2") (pinfunction "2_2") (pintype "passive"))
      (node (ref "U1") (pin "5") (pinfunction "FB_5") (pintype "bidirectional"))
    )
    (net (code "81") (name "Net-(U1-RCL)") (class "Default")
      (node (ref "R5") (pin "2") (pinfunction "2_2") (pintype "passive"))
      (node (ref "U1") (pin "3") (pinfunction "RCL_3") (pintype "input"))
    )
    (net (code "82") (name "Net-(U1-RT{slash}SD)") (class "Default")
      (node (ref "Ron_a") (pin "2") (pinfunction "2_2") (pintype "passive"))
      (node (ref "U1") (pin "6") (pinfunction "RT/SD_6") (pintype "input"))
    )
    (net (code "83") (name "Net-(U1-VCC)") (class "Default")
      (node (ref "C15") (pin "1") (pinfunction "1_1") (pintype "passive"))
      (node (ref "U1") (pin "7") (pinfunction "VCC_7") (pintype "power_in"))
    )
    (net (code "84") (name "Net-(U5V-Vout)") (class "Default")
      (node (ref "R17") (pin "1") (pinfunction "1_1") (pintype "passive"))
      (node (ref "U5V") (pin "3") (pinfunction "Vout_3") (pintype "output"))
    )
    (net (code "85") (name "Net-(U7-HBA)") (class "Default")
      (node (ref "C46") (pin "1") (pinfunction "1_1") (pintype "passive"))
      (node (ref "U7") (pin "26") (pinfunction "HBA_26") (pintype "passive"))
    )
    (net (code "86") (name "Net-(U7-HBB)") (class "Default")
      (node (ref "C54") (pin "1") (pinfunction "1_1") (pintype "passive"))
      (node (ref "U7") (pin "20") (pinfunction "HBB_20") (pintype "passive"))
    )
    (net (code "87") (name "Net-(U7-SDA)") (class "Default")
      (node (ref "R8_A") (pin "2") (pinfunction "2_2") (pintype "passive"))
      (node (ref "U7") (pin "2") (pinfunction "SDA_2") (pintype "input"))
    )
    (net (code "88") (name "Net-(U7-SIA)") (class "Default")
      (node (ref "R12_A") (pin "2") (pinfunction "2_2") (pintype "passive"))
      (node (ref "U7") (pin "1") (pinfunction "SIA_1") (pintype "input"))
    )
    (net (code "89") (name "Net-(U7-SIB)") (class "Default")
      (node (ref "R24") (pin "1") (pinfunction "1_1") (pintype "passive"))
      (node (ref "U7") (pin "14") (pinfunction "SIB_14") (pintype "input"))
    )
    (net (code "90") (name "Net-(U7-SOB)") (class "Default")
      (node (ref "R34") (pin "1") (pinfunction "1_1") (pintype "passive"))
      (node (ref "U7") (pin "13") (pinfunction "SOB_13") (pintype "output"))
    )
    (net (code "91") (name "PGND") (class "Default")
      (node (ref "C1") (pin "1") (pinfunction "1_1") (pintype "passive"))
      (node (ref "C10") (pin "1") (pinfunction "1_1") (pintype "passive"))
      (node (ref "C11") (pin "1") (pinfunction "1_1") (pintype "passive"))
      (node (ref "C12") (pin "1") (pinfunction "1_1") (pintype "passive"))
      (node (ref "C13") (pin "1") (pinfunction "1_1") (pintype "passive"))
      (node (ref "C16") (pin "1") (pinfunction "1_1") (pintype "passive"))
      (node (ref "C20") (pin "1") (pinfunction "1_1") (pintype "passive"))
      (node (ref "C25") (pin "1") (pinfunction "1_1") (pintype "passive"))
      (node (ref "C27") (pin "1") (pinfunction "1_1") (pintype "passive"))
      (node (ref "C28") (pin "1") (pinfunction "1_1") (pintype "passive"))
      (node (ref "C30") (pin "1") (pinfunction "1_1") (pintype "passive"))
      (node (ref "C36") (pin "1") (pinfunction "1_1") (pintype "passive"))
      (node (ref "C4") (pin "1") (pinfunction "1_1") (pintype "passive"))
      (node (ref "C41") (pin "1") (pinfunction "1_1") (pintype "passive"))
      (node (ref "C44") (pin "1") (pinfunction "1_1") (pintype "passive"))
      (node (ref "C45") (pin "1") (pinfunction "1_1") (pintype "passive"))
      (node (ref "C47") (pin "1") (pinfunction "1_1") (pintype "passive"))
      (node (ref "C5") (pin "1") (pinfunction "1_1") (pintype "passive"))
      (node (ref "C6") (pin "1") (pinfunction "1_1") (pintype "passive"))
      (node (ref "C7") (pin "1") (pinfunction "1_1") (pintype "passive"))
      (node (ref "C70") (pin "1") (pinfunction "1_1") (pintype "passive"))
      (node (ref "C72") (pin "1") (pinfunction "1_1") (pintype "passive"))
      (node (ref "C8") (pin "1") (pinfunction "1_1") (pintype "passive"))
      (node (ref "C9") (pin "1") (pinfunction "1_1") (pintype "passive"))
      (node (ref "D12") (pin "2") (pinfunction "A_2") (pintype "passive"))
      (node (ref "D14") (pin "1") (pinfunction "K_1") (pintype "passive"))
      (node (ref "D15") (pin "1") (pinfunction "K_1") (pintype "passive"))
      (node (ref "D9") (pin "2") (pinfunction "A_2") (pintype "passive"))
      (node (ref "Q3") (pin "3") (pinfunction "S_3") (pintype "passive"))
      (node (ref "Q4") (pin "3") (pinfunction "S_3") (pintype "passive"))
      (node (ref "R11") (pin "1") (pinfunction "1_1") (pintype "passive"))
      (node (ref "R14") (pin "1") (pinfunction "1_1") (pintype "passive"))
      (node (ref "R22") (pin "1") (pinfunction "1_1") (pintype "passive"))
      (node (ref "R23") (pin "2") (pinfunction "2_2") (pintype "passive"))
    )
    (net (code "92") (name "VIN_N") (class "Default")
      (node (ref "C10") (pin "2") (pinfunction "2_2") (pintype "passive"))
      (node (ref "C11") (pin "2") (pinfunction "2_2") (pintype "passive"))
      (node (ref "C12") (pin "2") (pinfunction "2_2") (pintype "passive"))
      (node (ref "C13") (pin "2") (pinfunction "2_2") (pintype "passive"))
      (node (ref "C4") (pin "2") (pinfunction "2_2") (pintype "passive"))
      (node (ref "C5") (pin "2") (pinfunction "2_2") (pintype "passive"))
      (node (ref "C6") (pin "2") (pinfunction "2_2") (pintype "passive"))
      (node (ref "C7") (pin "2") (pinfunction "2_2") (pintype "passive"))
      (node (ref "C70") (pin "2") (pinfunction "2_2") (pintype "passive"))
      (node (ref "C72") (pin "2") (pinfunction "2_2") (pintype "passive"))
      (node (ref "C8") (pin "2") (pinfunction "2_2") (pintype "passive"))
      (node (ref "C9") (pin "2") (pinfunction "2_2") (pintype "passive"))
      (node (ref "D13") (pin "1") (pinfunction "K_1") (pintype "passive"))
      (node (ref "Q1") (pin "2") (pinfunction "D_2") (pintype "passive"))
      (node (ref "R1") (pin "1") (pinfunction "1_1") (pintype "passive"))
      (node (ref "RB1_P") (pin "1") (pinfunction "1_1") (pintype "passive"))
    )
    (net (code "93") (name "VIN_P") (class "Default")
      (node (ref "C21") (pin "2") (pinfunction "2_2") (pintype "passive"))
      (node (ref "C22") (pin "2") (pinfunction "2_2") (pintype "passive"))
      (node (ref "C26") (pin "2") (pinfunction "2_2") (pintype "passive"))
      (node (ref "C64") (pin "2") (pinfunction "2_2") (pintype "passive"))
      (node (ref "D1_a") (pin "1") (pinfunction "K_1") (pintype "passive"))
      (node (ref "D1_b") (pin "1") (pinfunction "K_1") (pintype "passive"))
      (node (ref "D1_c") (pin "1") (pinfunction "K_1") (pintype "passive"))
      (node (ref "D1_d") (pin "1") (pinfunction "K_1") (pintype "passive"))
      (node (ref "D1_e") (pin "1") (pinfunction "K_1") (pintype "passive"))
      (node (ref "D1_f") (pin "1") (pinfunction "K_1") (pintype "passive"))
      (node (ref "D2_a") (pin "1") (pinfunction "K_1") (pintype "passive"))
      (node (ref "D2_b") (pin "1") (pinfunction "K_1") (pintype "passive"))
      (node (ref "D2_c") (pin "1") (pinfunction "K_1") (pintype "passive"))
      (node (ref "D2_d") (pin "1") (pinfunction "K_1") (pintype "passive"))
      (node (ref "D2_e") (pin "1") (pinfunction "K_1") (pintype "passive"))
      (node (ref "D2_f") (pin "1") (pinfunction "K_1") (pintype "passive"))
      (node (ref "D_CLAMP_1") (pin "1") (pinfunction "K_1") (pintype "passive"))
      (node (ref "R1") (pin "2") (pinfunction "2_2") (pintype "passive"))
      (node (ref "RB1_N") (pin "1") (pinfunction "1_1") (pintype "passive"))
      (node (ref "Ron_c") (pin "1") (pinfunction "1_1") (pintype "passive"))
      (node (ref "Ron_d") (pin "1") (pinfunction "1_1") (pintype "passive"))
      (node (ref "U1") (pin "8") (pinfunction "VIN_8") (pintype "input"))
    )
    (net (code "94") (name "VOUT_P") (class "Default")
      (node (ref "C1") (pin "2") (pinfunction "2_2") (pintype "passive"))
      (node (ref "C16") (pin "2") (pinfunction "2_2") (pintype "passive"))
      (node (ref "C20") (pin "2") (pinfunction "2_2") (pintype "passive"))
      (node (ref "C25") (pin "2") (pinfunction "2_2") (pintype "passive"))
      (node (ref "C27") (pin "2") (pinfunction "2_2") (pintype "passive"))
      (node (ref "C28") (pin "2") (pinfunction "2_2") (pintype "passive"))
      (node (ref "C30") (pin "2") (pinfunction "2_2") (pintype "passive"))
      (node (ref "C36") (pin "2") (pinfunction "2_2") (pintype "passive"))
      (node (ref "C41") (pin "2") (pinfunction "2_2") (pintype "passive"))
      (node (ref "C44") (pin "2") (pinfunction "2_2") (pintype "passive"))
      (node (ref "C45") (pin "2") (pinfunction "2_2") (pintype "passive"))
      (node (ref "C47") (pin "2") (pinfunction "2_2") (pintype "passive"))
      (node (ref "D7") (pin "1") (pinfunction "K_1") (pintype "passive"))
      (node (ref "Q2") (pin "2") (pinfunction "D_2") (pintype "passive"))
      (node (ref "R10") (pin "1") (pinfunction "1_1") (pintype "passive"))
      (node (ref "RA1_P") (pin "1") (pinfunction "1_1") (pintype "passive"))
    )
    (net (code "95") (name "unconnected-(J_IN-PadM)") (class "Default")
      (node (ref "J_IN") (pin "M") (pinfunction "M_M") (pintype "passive"))
    )
    (net (code "96") (name "unconnected-(J_OUT-PadM)") (class "Default")
      (node (ref "J_OUT") (pin "M") (pinfunction "M_M") (pintype "passive"))
    )
    (net (code "97") (name "unconnected-(U7-OVP-Pad15)") (class "Default")
      (node (ref "U7") (pin "15") (pinfunction "OVP_15") (pintype "passive"))
    )
  )
)
